# Timing_Control_V1p1.net
KiCad netlist of a schematic drawn in EAGLE
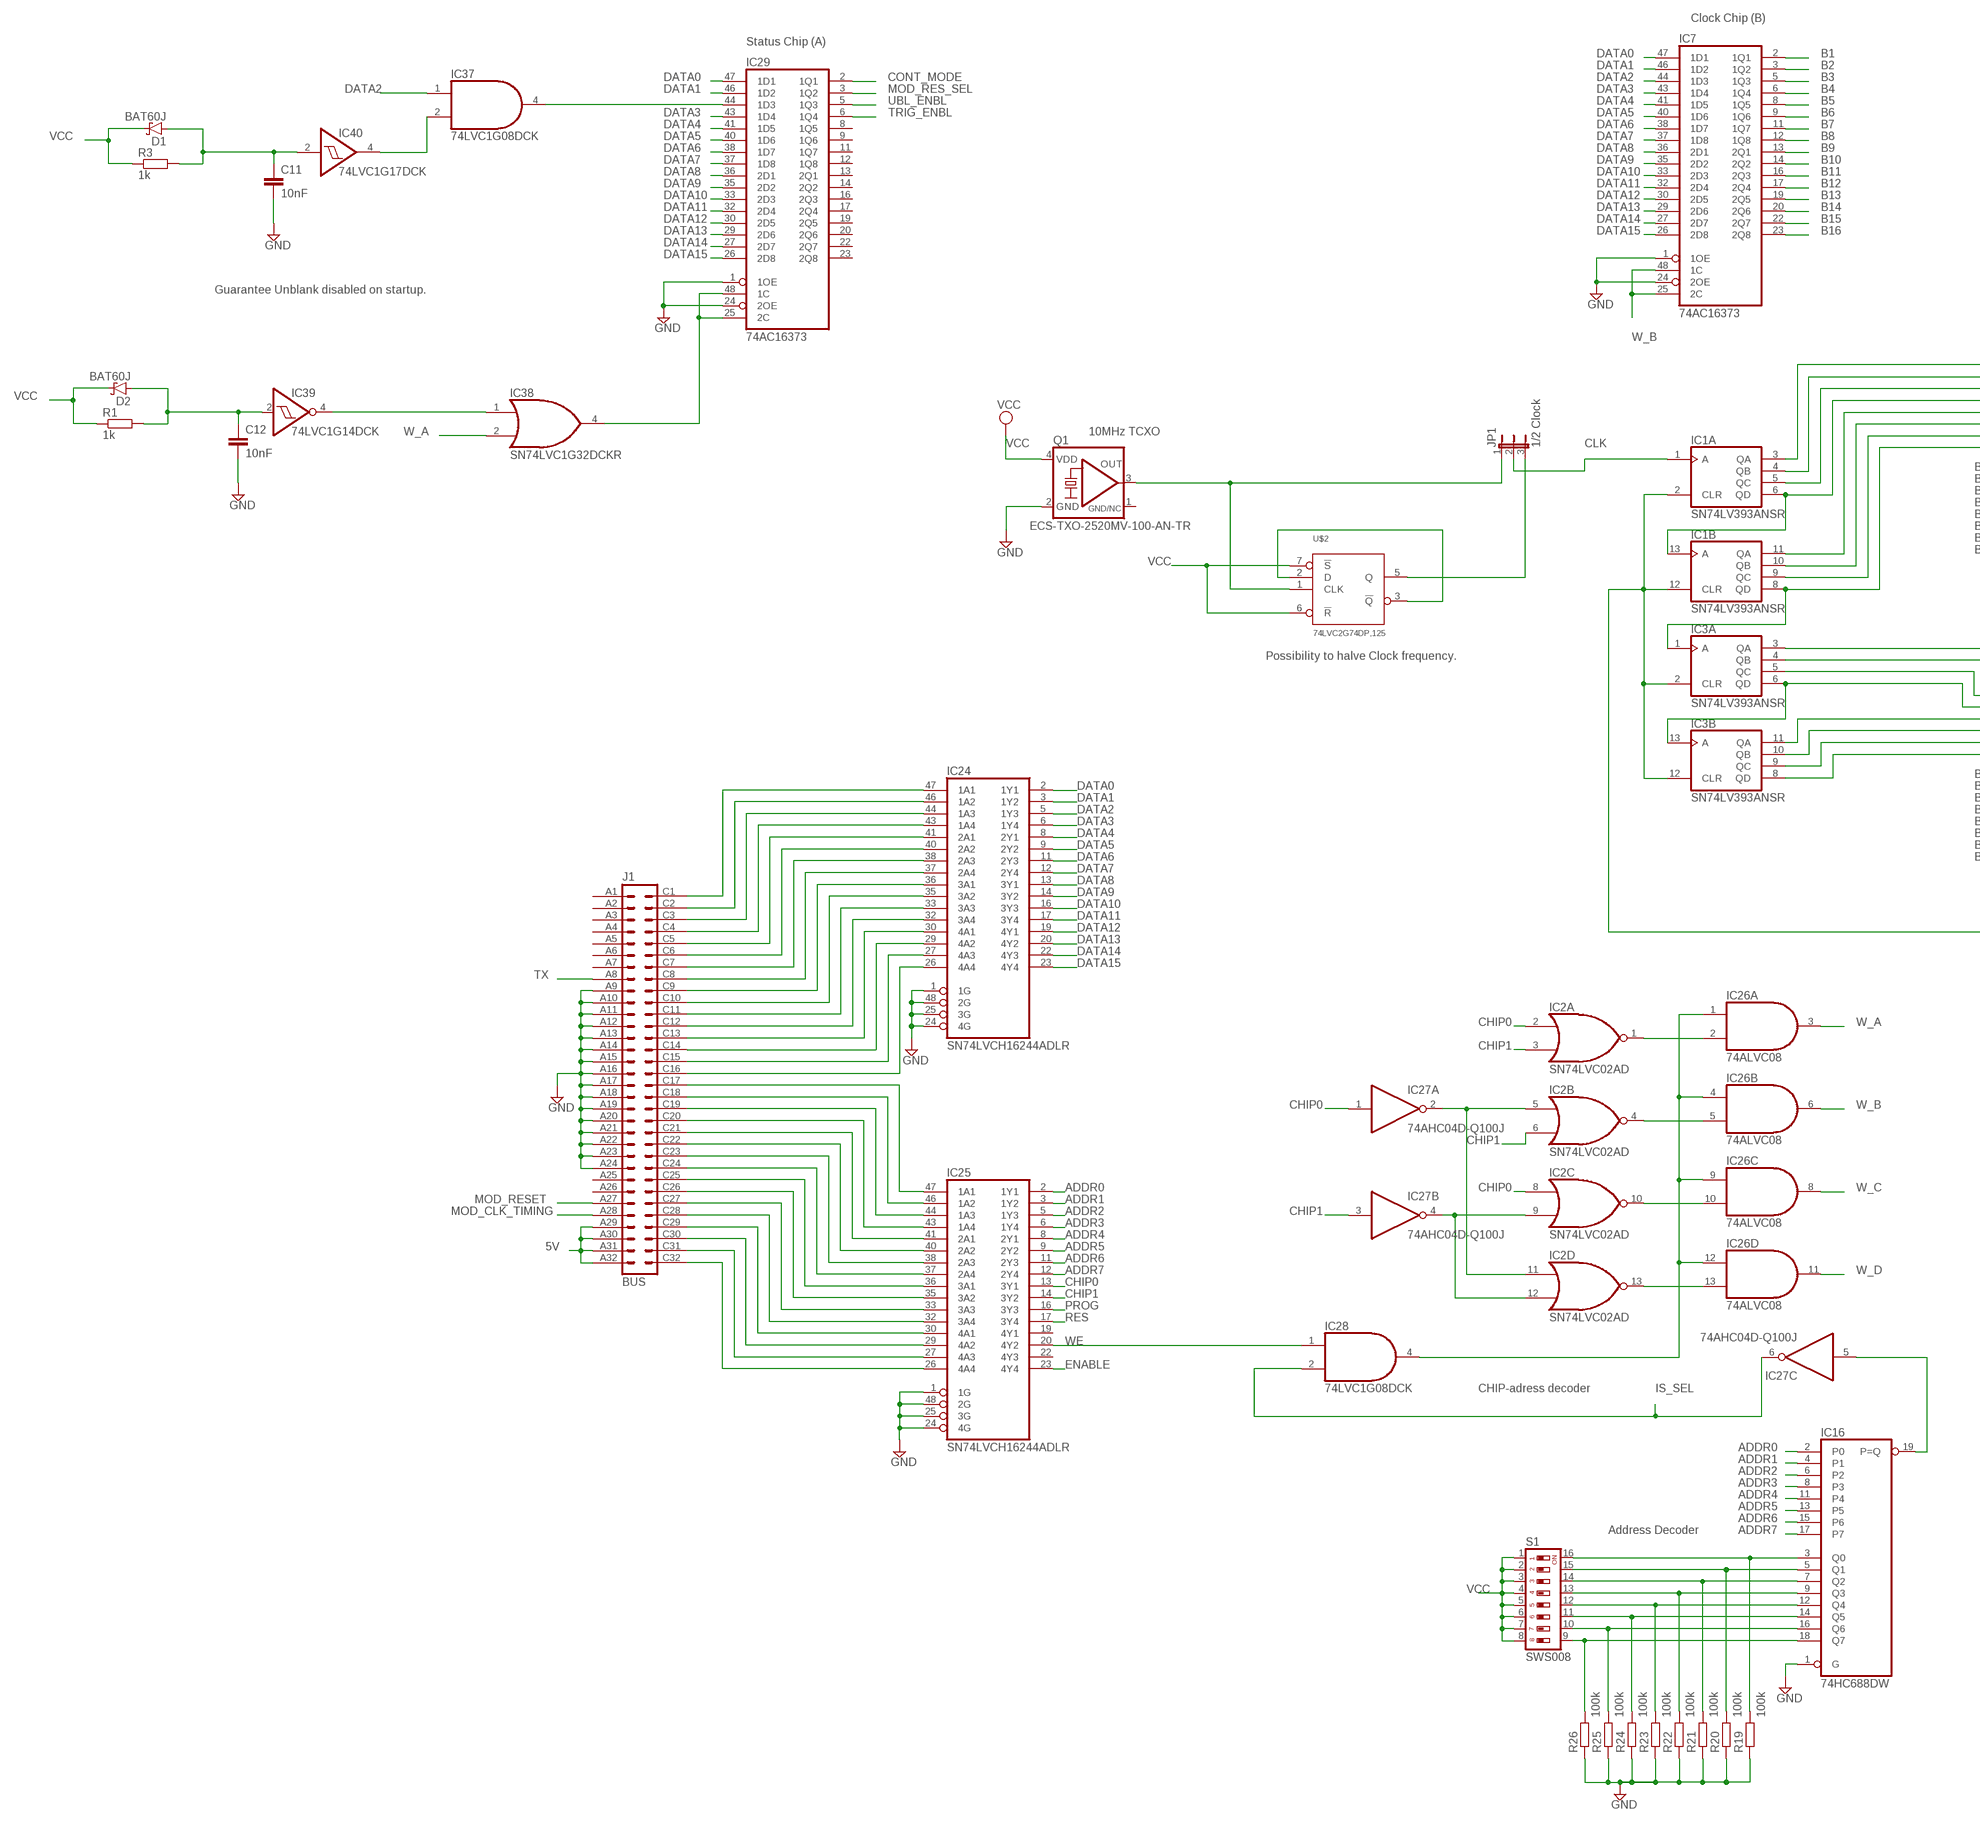
[diagram p0: schematic, sheet 1, part 1 of 3]
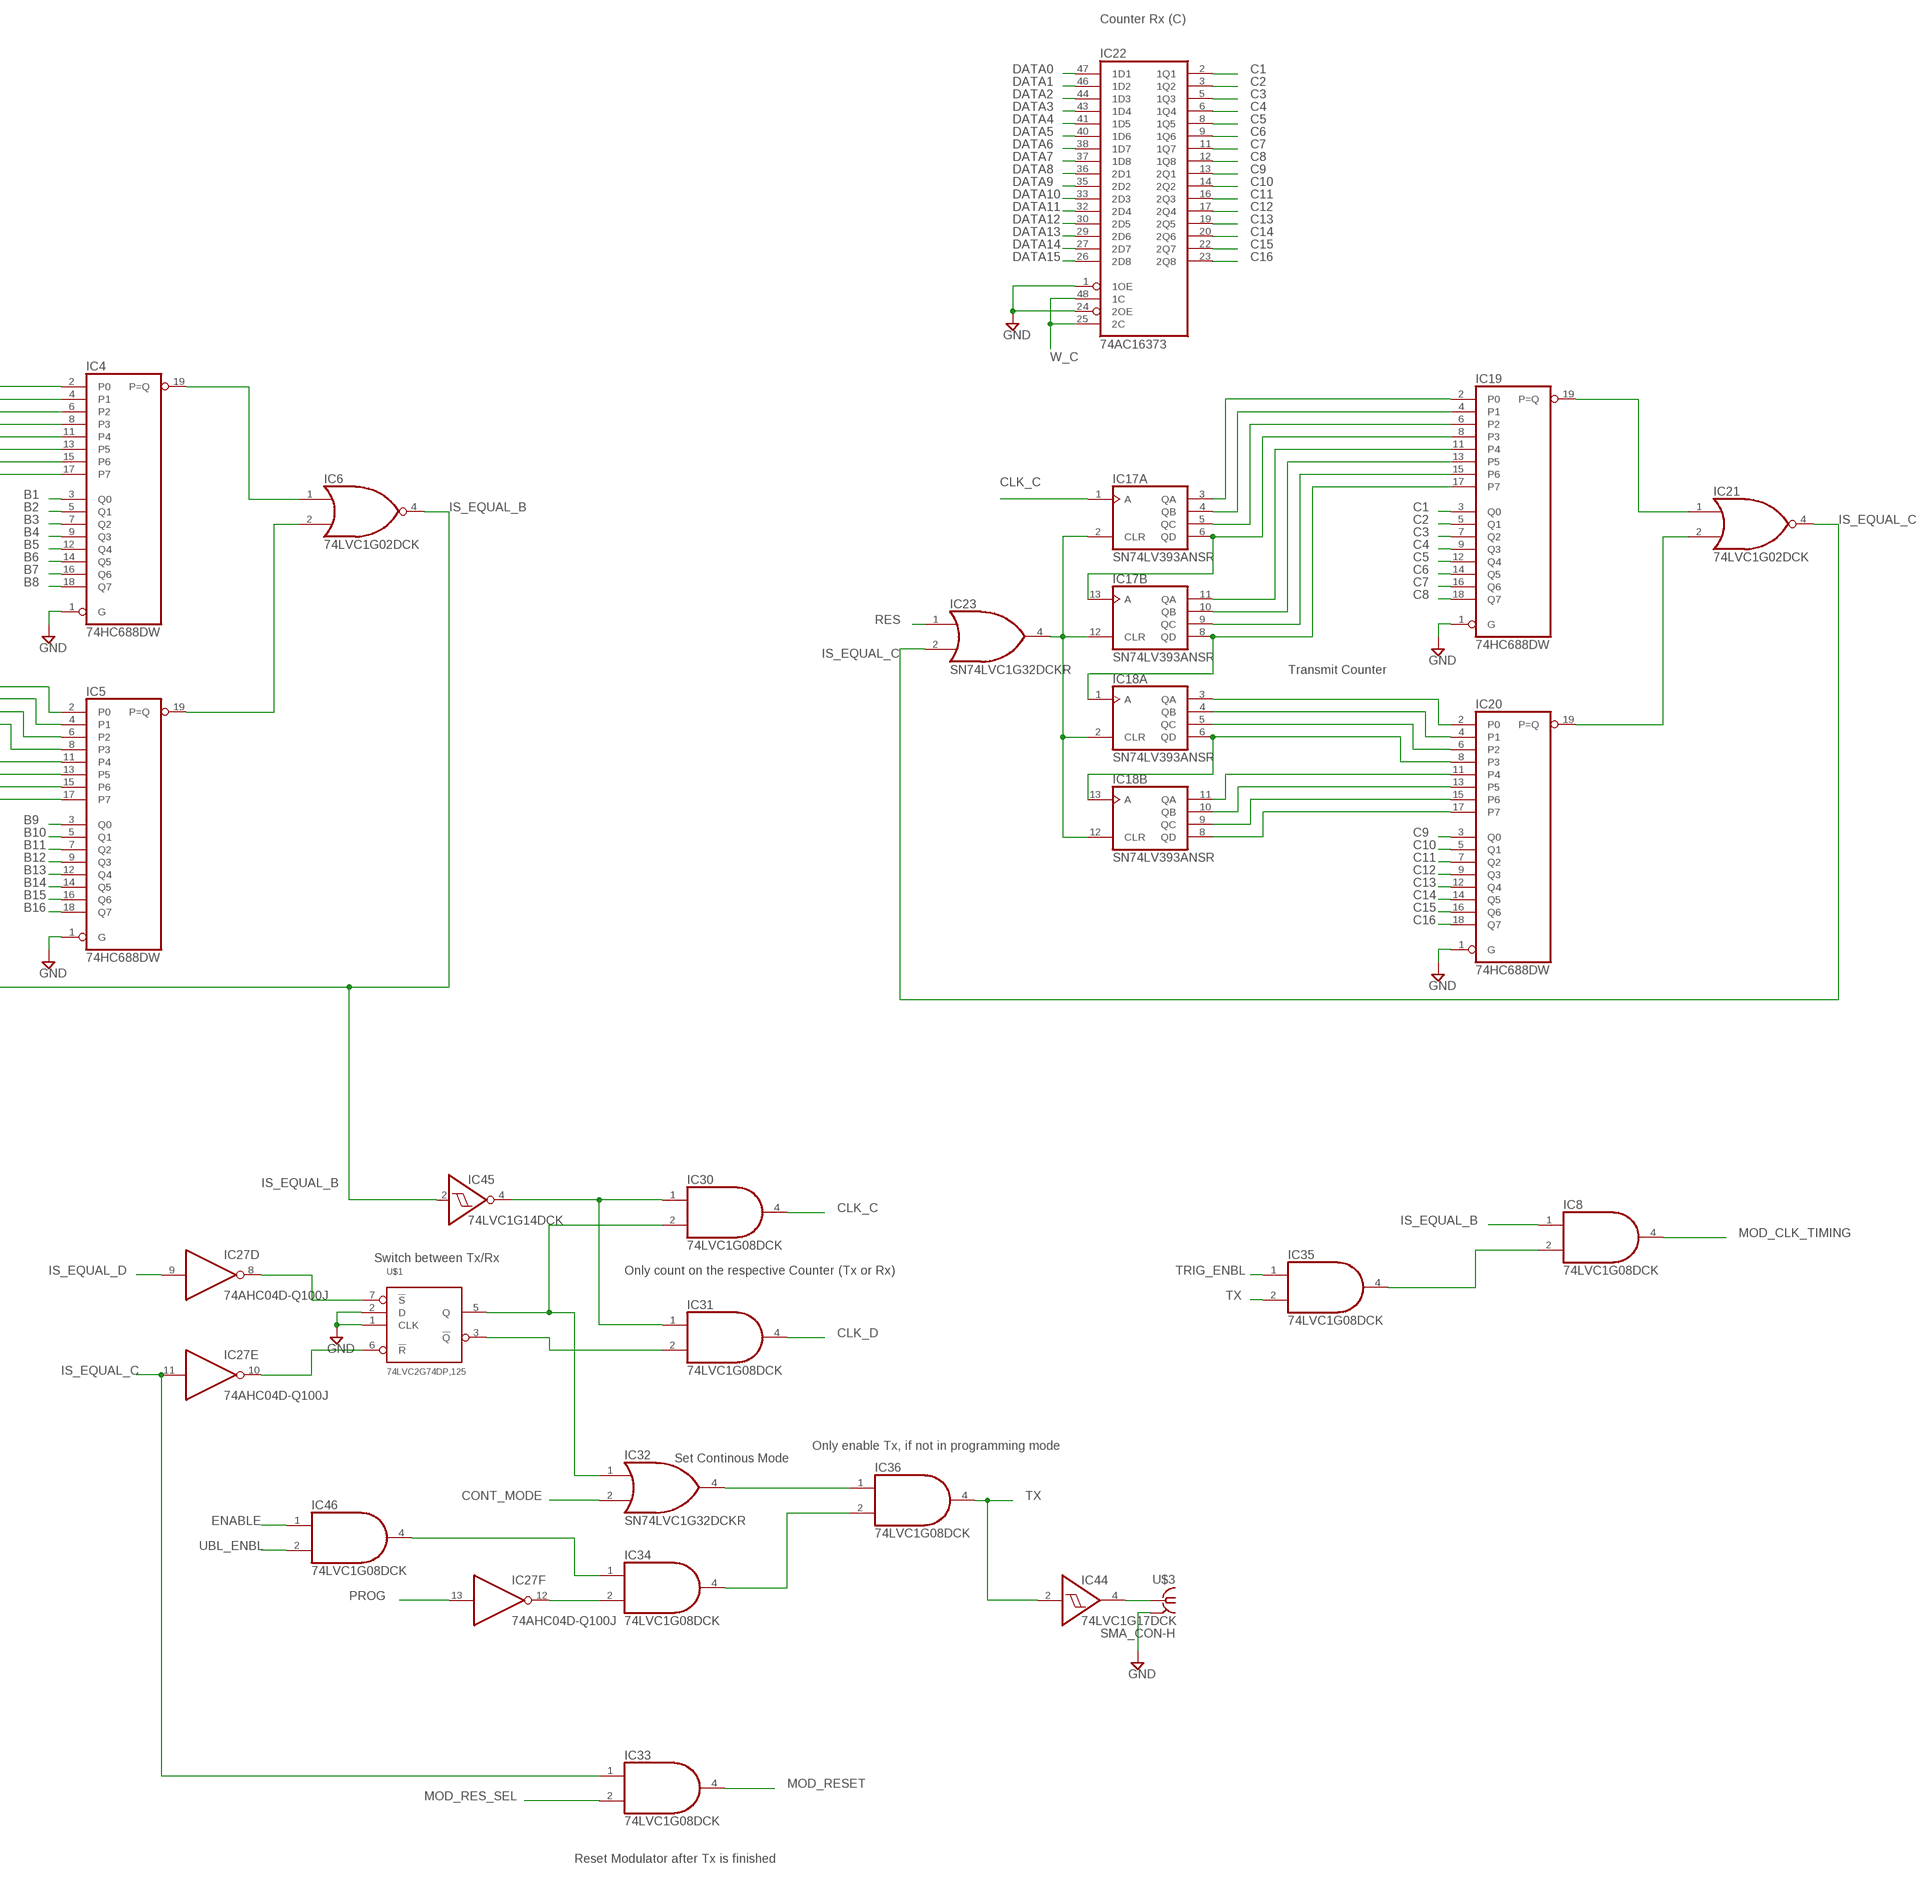
[diagram p1: schematic, sheet 1, part 2 of 3]
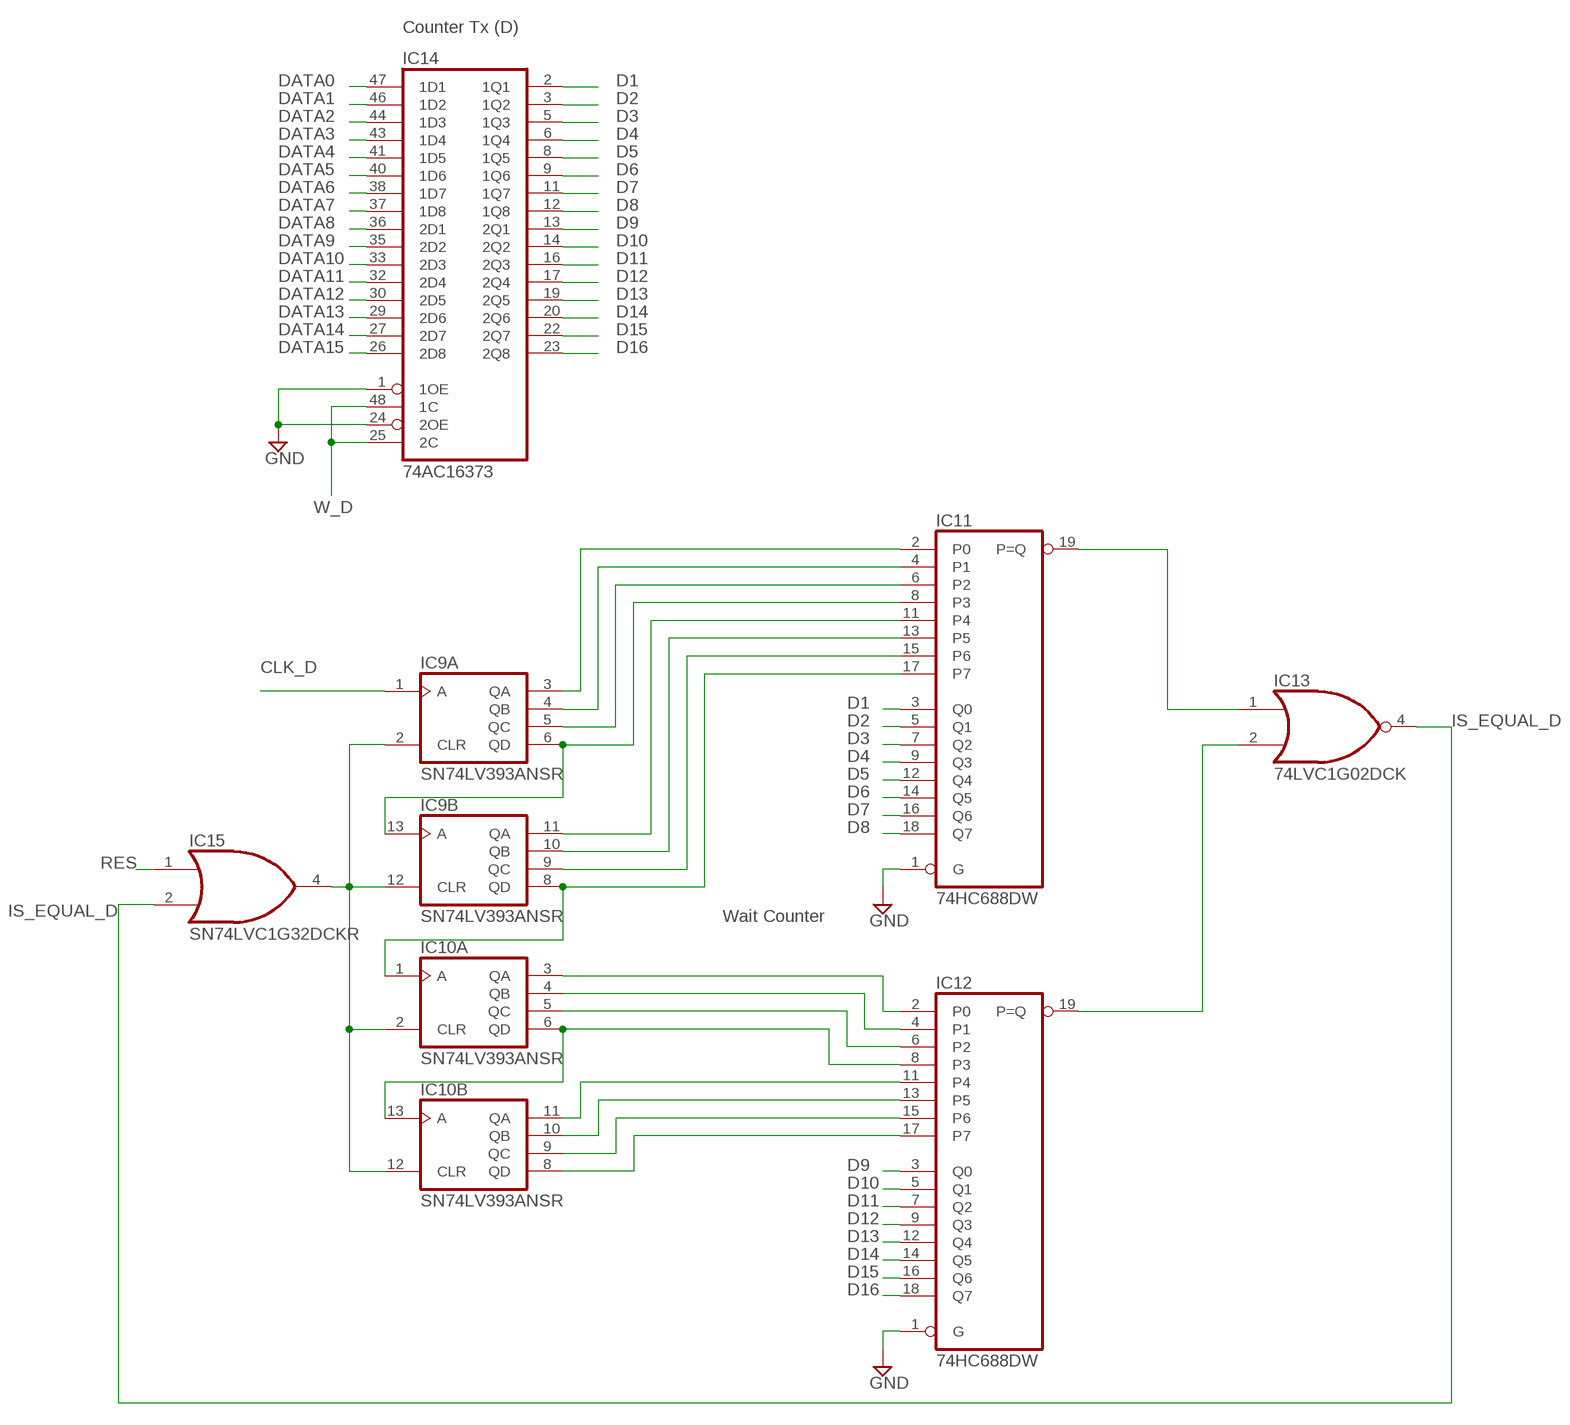
[diagram p2: schematic, sheet 1, part 3 of 3]
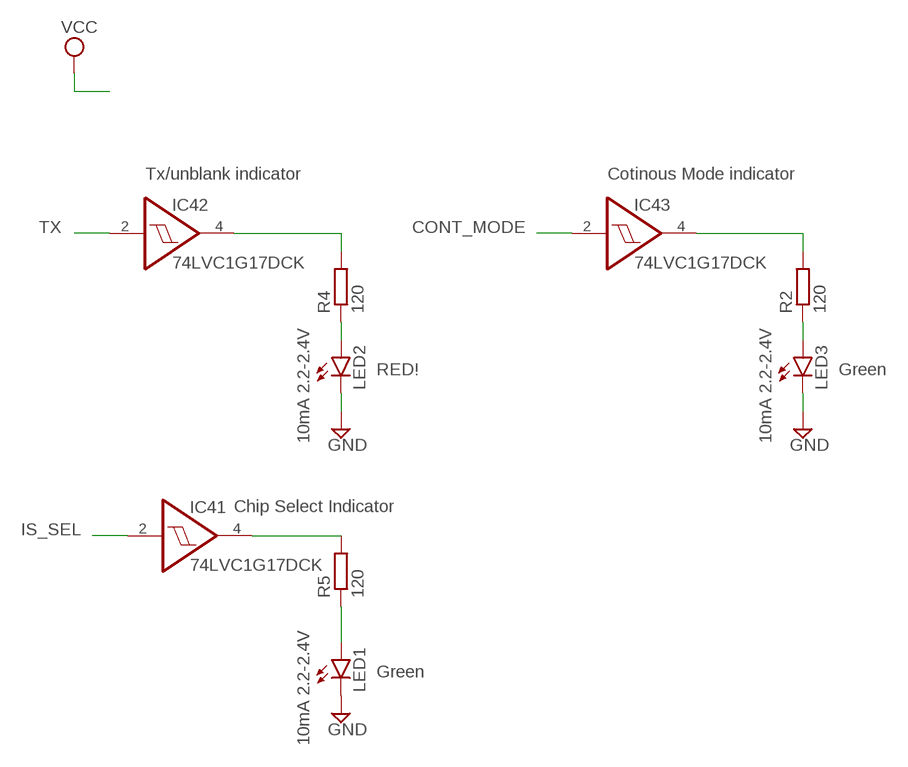
[diagram p3: schematic, sheet 2]
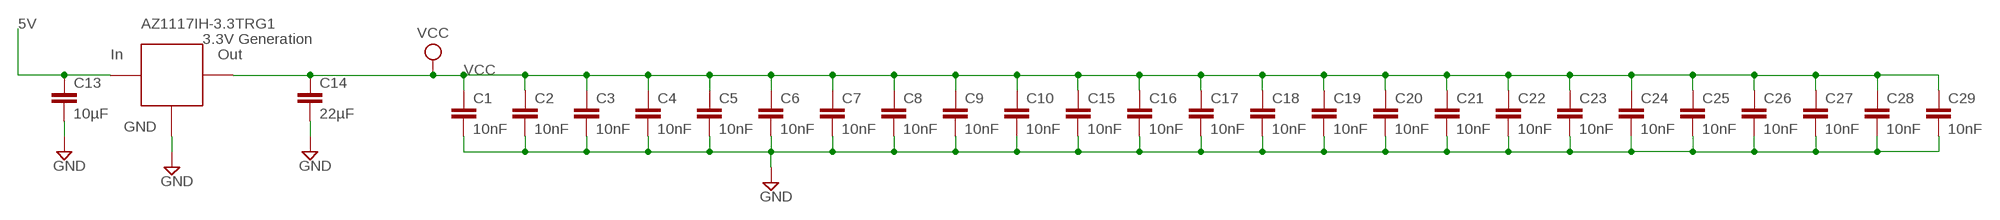
[diagram p4: schematic, sheet 3]

(export (version "E")
  (design (tool "Eeschema 10.0.6"))
  (components
    (comp (ref "C11")
      (value "10nF")
      (footprint "eagle-import:C0603")
      (libsource (lib "eagle-import") (part "C-EUC0603"))
    )
    (comp (ref "C12")
      (value "10nF")
      (footprint "eagle-import:C0603")
      (libsource (lib "eagle-import") (part "C-EUC0603"))
    )
    (comp (ref "D1")
      (value "BAT60J")
      (footprint "eagle-import:SOD323_ST")
      (libsource (lib "eagle-import") (part "BAT60J"))
    )
    (comp (ref "D2")
      (value "BAT60J")
      (footprint "eagle-import:SOD323_ST")
      (libsource (lib "eagle-import") (part "BAT60J"))
    )
    (comp (ref "IC1")
      (value "SN74LV393ANSR")
      (footprint "eagle-import:SO14")
      (libsource (lib "eagle-import") (part "74393DAC"))
    )
    (comp (ref "IC2")
      (value "SN74LVC02AD")
      (footprint "eagle-import:SO14")
      (libsource (lib "eagle-import") (part "7402DAS"))
    )
    (comp (ref "IC3")
      (value "SN74LV393ANSR")
      (footprint "eagle-import:SO14")
      (libsource (lib "eagle-import") (part "74393DAC"))
    )
    (comp (ref "IC4")
      (value "74HC688DW")
      (footprint "eagle-import:SO20W")
      (libsource (lib "eagle-import") (part "74688DWHC"))
    )
    (comp (ref "IC5")
      (value "74HC688DW")
      (footprint "eagle-import:SO20W")
      (libsource (lib "eagle-import") (part "74688DWHC"))
    )
    (comp (ref "IC6")
      (value "74LVC1G02DCK")
      (footprint "eagle-import:SC70-5")
      (libsource (lib "eagle-import") (part "741G02DCKLVC"))
    )
    (comp (ref "IC7")
      (value "74AC16373")
      (footprint "eagle-import:SSOP48DL")
      (libsource (lib "eagle-import") (part "74AC16373"))
    )
    (comp (ref "IC8")
      (value "74LVC1G08DCK")
      (footprint "eagle-import:SC70-5")
      (libsource (lib "eagle-import") (part "741G08DCKLVC"))
    )
    (comp (ref "IC9")
      (value "SN74LV393ANSR")
      (footprint "eagle-import:SO14")
      (libsource (lib "eagle-import") (part "74393DAC"))
    )
    (comp (ref "IC10")
      (value "SN74LV393ANSR")
      (footprint "eagle-import:SO14")
      (libsource (lib "eagle-import") (part "74393DAC"))
    )
    (comp (ref "IC11")
      (value "74HC688DW")
      (footprint "eagle-import:SO20W")
      (libsource (lib "eagle-import") (part "74688DWHC"))
    )
    (comp (ref "IC12")
      (value "74HC688DW")
      (footprint "eagle-import:SO20W")
      (libsource (lib "eagle-import") (part "74688DWHC"))
    )
    (comp (ref "IC13")
      (value "74LVC1G02DCK")
      (footprint "eagle-import:SC70-5")
      (libsource (lib "eagle-import") (part "741G02DCKLVC"))
    )
    (comp (ref "IC14")
      (value "74AC16373")
      (footprint "eagle-import:SSOP48DL")
      (libsource (lib "eagle-import") (part "74AC16373"))
    )
    (comp (ref "IC15")
      (value "SN74LVC1G32DCKR")
      (footprint "eagle-import:SC70-5")
      (libsource (lib "eagle-import") (part "741G32DCKAUC"))
    )
    (comp (ref "IC16")
      (value "74HC688DW")
      (footprint "eagle-import:SO20W")
      (libsource (lib "eagle-import") (part "74688DWHC"))
    )
    (comp (ref "IC17")
      (value "SN74LV393ANSR")
      (footprint "eagle-import:SO14")
      (libsource (lib "eagle-import") (part "74393DAC"))
    )
    (comp (ref "IC18")
      (value "SN74LV393ANSR")
      (footprint "eagle-import:SO14")
      (libsource (lib "eagle-import") (part "74393DAC"))
    )
    (comp (ref "IC19")
      (value "74HC688DW")
      (footprint "eagle-import:SO20W")
      (libsource (lib "eagle-import") (part "74688DWHC"))
    )
    (comp (ref "IC20")
      (value "74HC688DW")
      (footprint "eagle-import:SO20W")
      (libsource (lib "eagle-import") (part "74688DWHC"))
    )
    (comp (ref "IC21")
      (value "74LVC1G02DCK")
      (footprint "eagle-import:SC70-5")
      (libsource (lib "eagle-import") (part "741G02DCKLVC"))
    )
    (comp (ref "IC22")
      (value "74AC16373")
      (footprint "eagle-import:SSOP48DL")
      (libsource (lib "eagle-import") (part "74AC16373"))
    )
    (comp (ref "IC23")
      (value "SN74LVC1G32DCKR")
      (footprint "eagle-import:SC70-5")
      (libsource (lib "eagle-import") (part "741G32DCKAUC"))
    )
    (comp (ref "IC24")
      (value "SN74LVCH16244ADLR")
      (footprint "eagle-import:SSOP48DL")
      (libsource (lib "eagle-import") (part "74AC16244"))
    )
    (comp (ref "IC25")
      (value "SN74LVCH16244ADLR")
      (footprint "eagle-import:SSOP48DL")
      (libsource (lib "eagle-import") (part "74AC16244"))
    )
    (comp (ref "IC26")
      (value "74ALVC08")
      (footprint "eagle-import:SO14")
      (libsource (lib "eagle-import") (part "7408DALS"))
    )
    (comp (ref "IC27")
      (value "74AHC04D-Q100J")
      (footprint "eagle-import:SO14")
      (libsource (lib "eagle-import") (part "7404DALS"))
    )
    (comp (ref "IC28")
      (value "74LVC1G08DCK")
      (footprint "eagle-import:SC70-5")
      (libsource (lib "eagle-import") (part "741G08DCKLVC"))
    )
    (comp (ref "IC29")
      (value "74AC16373")
      (footprint "eagle-import:SSOP48DL")
      (libsource (lib "eagle-import") (part "74AC16373"))
    )
    (comp (ref "IC30")
      (value "74LVC1G08DCK")
      (footprint "eagle-import:SC70-5")
      (libsource (lib "eagle-import") (part "741G08DCKLVC"))
    )
    (comp (ref "IC31")
      (value "74LVC1G08DCK")
      (footprint "eagle-import:SC70-5")
      (libsource (lib "eagle-import") (part "741G08DCKLVC"))
    )
    (comp (ref "IC32")
      (value "SN74LVC1G32DCKR")
      (footprint "eagle-import:SC70-5")
      (libsource (lib "eagle-import") (part "741G32DCKAUC"))
    )
    (comp (ref "IC33")
      (value "74LVC1G08DCK")
      (footprint "eagle-import:SC70-5")
      (libsource (lib "eagle-import") (part "741G08DCKLVC"))
    )
    (comp (ref "IC34")
      (value "74LVC1G08DCK")
      (footprint "eagle-import:SC70-5")
      (libsource (lib "eagle-import") (part "741G08DCKLVC"))
    )
    (comp (ref "IC35")
      (value "74LVC1G08DCK")
      (footprint "eagle-import:SC70-5")
      (libsource (lib "eagle-import") (part "741G08DCKLVC"))
    )
    (comp (ref "IC36")
      (value "74LVC1G08DCK")
      (footprint "eagle-import:SC70-5")
      (libsource (lib "eagle-import") (part "741G08DCKLVC"))
    )
    (comp (ref "IC37")
      (value "74LVC1G08DCK")
      (footprint "eagle-import:SC70-5")
      (libsource (lib "eagle-import") (part "741G08DCKLVC"))
    )
    (comp (ref "IC38")
      (value "SN74LVC1G32DCKR")
      (footprint "eagle-import:SC70-5")
      (libsource (lib "eagle-import") (part "741G32DCKAUC"))
    )
    (comp (ref "IC39")
      (value "74LVC1G14DCK")
      (footprint "eagle-import:SC70-5")
      (libsource (lib "eagle-import") (part "741G14DCKLVC"))
    )
    (comp (ref "IC40")
      (value "74LVC1G17DCK")
      (footprint "eagle-import:SC70-5")
      (libsource (lib "eagle-import") (part "741G17DCKLVC"))
    )
    (comp (ref "IC44")
      (value "74LVC1G17DCK")
      (footprint "eagle-import:SC70-5")
      (libsource (lib "eagle-import") (part "741G17DCKLVC"))
    )
    (comp (ref "IC45")
      (value "74LVC1G14DCK")
      (footprint "eagle-import:SC70-5")
      (libsource (lib "eagle-import") (part "741G14DCKLVC"))
    )
    (comp (ref "IC46")
      (value "74LVC1G08DCK")
      (footprint "eagle-import:SC70-5")
      (libsource (lib "eagle-import") (part "741G08DCKLVC"))
    )
    (comp (ref "J1")
      (value "BUS")
      (footprint "eagle-import:VG64P")
      (libsource (lib "eagle-import") (part "VG64P"))
    )
    (comp (ref "JP1")
      (value "1/2 Clock")
      (footprint "eagle-import:JP2")
      (libsource (lib "eagle-import") (part "JP2E"))
    )
    (comp (ref "Q1")
      (value "ECS-TXO-2520MV-100-AN-TR")
      (footprint "eagle-import:2.5X2.0_KXO-86-TCXO")
      (libsource (lib "eagle-import") (part "KXO-TCXO-CMOS-86"))
    )
    (comp (ref "R1")
      (value "1k")
      (footprint "eagle-import:R0603")
      (libsource (lib "eagle-import") (part "R-EU_R0603"))
    )
    (comp (ref "R3")
      (value "1k")
      (footprint "eagle-import:R0603")
      (libsource (lib "eagle-import") (part "R-EU_R0603"))
    )
    (comp (ref "R19")
      (value "100k")
      (footprint "eagle-import:R0603")
      (libsource (lib "eagle-import") (part "R-EU_R0603"))
    )
    (comp (ref "R20")
      (value "100k")
      (footprint "eagle-import:R0603")
      (libsource (lib "eagle-import") (part "R-EU_R0603"))
    )
    (comp (ref "R21")
      (value "100k")
      (footprint "eagle-import:R0603")
      (libsource (lib "eagle-import") (part "R-EU_R0603"))
    )
    (comp (ref "R22")
      (value "100k")
      (footprint "eagle-import:R0603")
      (libsource (lib "eagle-import") (part "R-EU_R0603"))
    )
    (comp (ref "R23")
      (value "100k")
      (footprint "eagle-import:R0603")
      (libsource (lib "eagle-import") (part "R-EU_R0603"))
    )
    (comp (ref "R24")
      (value "100k")
      (footprint "eagle-import:R0603")
      (libsource (lib "eagle-import") (part "R-EU_R0603"))
    )
    (comp (ref "R25")
      (value "100k")
      (footprint "eagle-import:R0603")
      (libsource (lib "eagle-import") (part "R-EU_R0603"))
    )
    (comp (ref "R26")
      (value "100k")
      (footprint "eagle-import:R0603")
      (libsource (lib "eagle-import") (part "R-EU_R0603"))
    )
    (comp (ref "S1")
      (value "SWS008")
      (footprint "eagle-import:SMS-008")
      (libsource (lib "eagle-import") (part "SWS008"))
    )
    (comp (ref "U$1")
      (value "74LVC2G74DP,125")
      (footprint "eagle-import:SSOP08")
      (libsource (lib "eagle-import") (part "74LVC2G74"))
    )
    (comp (ref "U$2")
      (value "74LVC2G74DP,125")
      (footprint "eagle-import:SSOP08")
      (libsource (lib "eagle-import") (part "74LVC2G74"))
    )
    (comp (ref "U$3")
      (value "SMA_CON-H")
      (footprint "eagle-import:BU-SMA-H")
      (libsource (lib "eagle-import") (part "SMA_CON-H"))
    )
    (comp (ref "C1")
      (value "10nF")
      (footprint "eagle-import:C0603")
      (libsource (lib "eagle-import") (part "C-EUC0603"))
    )
    (comp (ref "C2")
      (value "10nF")
      (footprint "eagle-import:C0603")
      (libsource (lib "eagle-import") (part "C-EUC0603"))
    )
    (comp (ref "C3")
      (value "10nF")
      (footprint "eagle-import:C0603")
      (libsource (lib "eagle-import") (part "C-EUC0603"))
    )
    (comp (ref "C4")
      (value "10nF")
      (footprint "eagle-import:C0603")
      (libsource (lib "eagle-import") (part "C-EUC0603"))
    )
    (comp (ref "C5")
      (value "10nF")
      (footprint "eagle-import:C0603")
      (libsource (lib "eagle-import") (part "C-EUC0603"))
    )
    (comp (ref "C6")
      (value "10nF")
      (footprint "eagle-import:C0603")
      (libsource (lib "eagle-import") (part "C-EUC0603"))
    )
    (comp (ref "C7")
      (value "10nF")
      (footprint "eagle-import:C0603")
      (libsource (lib "eagle-import") (part "C-EUC0603"))
    )
    (comp (ref "C8")
      (value "10nF")
      (footprint "eagle-import:C0603")
      (libsource (lib "eagle-import") (part "C-EUC0603"))
    )
    (comp (ref "C9")
      (value "10nF")
      (footprint "eagle-import:C0603")
      (libsource (lib "eagle-import") (part "C-EUC0603"))
    )
    (comp (ref "C10")
      (value "10nF")
      (footprint "eagle-import:C0603")
      (libsource (lib "eagle-import") (part "C-EUC0603"))
    )
    (comp (ref "C13")
      (value "10µF")
      (footprint "eagle-import:C1206")
      (libsource (lib "eagle-import") (part "C-EUC1206"))
    )
    (comp (ref "C14")
      (value "22µF")
      (footprint "eagle-import:C1206")
      (libsource (lib "eagle-import") (part "C-EUC1206"))
    )
    (comp (ref "C15")
      (value "10nF")
      (footprint "eagle-import:C0603")
      (libsource (lib "eagle-import") (part "C-EUC0603"))
    )
    (comp (ref "C16")
      (value "10nF")
      (footprint "eagle-import:C0603")
      (libsource (lib "eagle-import") (part "C-EUC0603"))
    )
    (comp (ref "C17")
      (value "10nF")
      (footprint "eagle-import:C0603")
      (libsource (lib "eagle-import") (part "C-EUC0603"))
    )
    (comp (ref "C18")
      (value "10nF")
      (footprint "eagle-import:C0603")
      (libsource (lib "eagle-import") (part "C-EUC0603"))
    )
    (comp (ref "C19")
      (value "10nF")
      (footprint "eagle-import:C0603")
      (libsource (lib "eagle-import") (part "C-EUC0603"))
    )
    (comp (ref "C20")
      (value "10nF")
      (footprint "eagle-import:C0603")
      (libsource (lib "eagle-import") (part "C-EUC0603"))
    )
    (comp (ref "C21")
      (value "10nF")
      (footprint "eagle-import:C0603")
      (libsource (lib "eagle-import") (part "C-EUC0603"))
    )
    (comp (ref "C22")
      (value "10nF")
      (footprint "eagle-import:C0603")
      (libsource (lib "eagle-import") (part "C-EUC0603"))
    )
    (comp (ref "C23")
      (value "10nF")
      (footprint "eagle-import:C0603")
      (libsource (lib "eagle-import") (part "C-EUC0603"))
    )
    (comp (ref "C24")
      (value "10nF")
      (footprint "eagle-import:C0603")
      (libsource (lib "eagle-import") (part "C-EUC0603"))
    )
    (comp (ref "C25")
      (value "10nF")
      (footprint "eagle-import:C0603")
      (libsource (lib "eagle-import") (part "C-EUC0603"))
    )
    (comp (ref "C26")
      (value "10nF")
      (footprint "eagle-import:C0603")
      (libsource (lib "eagle-import") (part "C-EUC0603"))
    )
    (comp (ref "C27")
      (value "10nF")
      (footprint "eagle-import:C0603")
      (libsource (lib "eagle-import") (part "C-EUC0603"))
    )
    (comp (ref "C28")
      (value "10nF")
      (footprint "eagle-import:C0603")
      (libsource (lib "eagle-import") (part "C-EUC0603"))
    )
    (comp (ref "C29")
      (value "10nF")
      (footprint "eagle-import:C0603")
      (libsource (lib "eagle-import") (part "C-EUC0603"))
    )
    (comp (ref "U$9")
      (value "AZ1117IH-3.3TRG1")
      (footprint "eagle-import:SOT223")
      (libsource (lib "eagle-import") (part "LT1117"))
    )
    (comp (ref "IC41")
      (value "74LVC1G17DCK")
      (footprint "eagle-import:SC70-5")
      (libsource (lib "eagle-import") (part "741G17DCKLVC"))
    )
    (comp (ref "IC42")
      (value "74LVC1G17DCK")
      (footprint "eagle-import:SC70-5")
      (libsource (lib "eagle-import") (part "741G17DCKLVC"))
    )
    (comp (ref "IC43")
      (value "74LVC1G17DCK")
      (footprint "eagle-import:SC70-5")
      (libsource (lib "eagle-import") (part "741G17DCKLVC"))
    )
    (comp (ref "LED1")
      (value "10mA 2.2-2.4V")
      (footprint "eagle-import:LED3MM")
      (libsource (lib "eagle-import") (part "LED3MM"))
    )
    (comp (ref "LED2")
      (value "10mA 2.2-2.4V")
      (footprint "eagle-import:LED3MM")
      (libsource (lib "eagle-import") (part "LED3MM"))
    )
    (comp (ref "LED3")
      (value "10mA 2.2-2.4V")
      (footprint "eagle-import:LED3MM")
      (libsource (lib "eagle-import") (part "LED3MM"))
    )
    (comp (ref "R2")
      (value "120")
      (footprint "eagle-import:R0603")
      (libsource (lib "eagle-import") (part "R-EU_R0603"))
    )
    (comp (ref "R4")
      (value "120")
      (footprint "eagle-import:R0603")
      (libsource (lib "eagle-import") (part "R-EU_R0603"))
    )
    (comp (ref "R5")
      (value "120")
      (footprint "eagle-import:R0603")
      (libsource (lib "eagle-import") (part "R-EU_R0603"))
    )
  )
  (nets
    (net (code "1") (name "5V") (class "Default")
      (node (ref "C13") (pin "1") (pinfunction "1_1") (pintype "passive"))
      (node (ref "J1") (pin "A29") (pinfunction "A29_A29") (pintype "passive"))
      (node (ref "J1") (pin "A30") (pinfunction "A30_A30") (pintype "passive"))
      (node (ref "J1") (pin "A31") (pinfunction "A31_A31") (pintype "passive"))
      (node (ref "J1") (pin "A32") (pinfunction "A32_A32") (pintype "passive"))
      (node (ref "U$9") (pin "3") (pinfunction "IN_3") (pintype "bidirectional"))
    )
    (net (code "2") (name "ADDR0") (class "Default")
      (node (ref "IC16") (pin "2") (pinfunction "P0_2") (pintype "input"))
      (node (ref "IC25") (pin "2") (pinfunction "1Y1_2") (pintype "tri_state"))
    )
    (net (code "3") (name "ADDR1") (class "Default")
      (node (ref "IC16") (pin "4") (pinfunction "P1_4") (pintype "input"))
      (node (ref "IC25") (pin "3") (pinfunction "1Y2_3") (pintype "tri_state"))
    )
    (net (code "4") (name "ADDR2") (class "Default")
      (node (ref "IC16") (pin "6") (pinfunction "P2_6") (pintype "input"))
      (node (ref "IC25") (pin "5") (pinfunction "1Y3_5") (pintype "tri_state"))
    )
    (net (code "5") (name "ADDR3") (class "Default")
      (node (ref "IC16") (pin "8") (pinfunction "P3_8") (pintype "input"))
      (node (ref "IC25") (pin "6") (pinfunction "1Y4_6") (pintype "tri_state"))
    )
    (net (code "6") (name "ADDR4") (class "Default")
      (node (ref "IC16") (pin "11") (pinfunction "P4_11") (pintype "input"))
      (node (ref "IC25") (pin "8") (pinfunction "2Y1_8") (pintype "tri_state"))
    )
    (net (code "7") (name "ADDR5") (class "Default")
      (node (ref "IC16") (pin "13") (pinfunction "P5_13") (pintype "input"))
      (node (ref "IC25") (pin "9") (pinfunction "2Y2_9") (pintype "tri_state"))
    )
    (net (code "8") (name "ADDR6") (class "Default")
      (node (ref "IC16") (pin "15") (pinfunction "P6_15") (pintype "input"))
      (node (ref "IC25") (pin "11") (pinfunction "2Y3_11") (pintype "tri_state"))
    )
    (net (code "9") (name "ADDR7") (class "Default")
      (node (ref "IC16") (pin "17") (pinfunction "P7_17") (pintype "input"))
      (node (ref "IC25") (pin "12") (pinfunction "2Y4_12") (pintype "tri_state"))
    )
    (net (code "10") (name "B1") (class "Default")
      (node (ref "IC4") (pin "3") (pinfunction "Q0_3") (pintype "input"))
      (node (ref "IC7") (pin "2") (pinfunction "1Q1_2") (pintype "tri_state"))
    )
    (net (code "11") (name "B2") (class "Default")
      (node (ref "IC4") (pin "5") (pinfunction "Q1_5") (pintype "input"))
      (node (ref "IC7") (pin "3") (pinfunction "1Q2_3") (pintype "tri_state"))
    )
    (net (code "12") (name "B3") (class "Default")
      (node (ref "IC4") (pin "7") (pinfunction "Q2_7") (pintype "input"))
      (node (ref "IC7") (pin "5") (pinfunction "1Q3_5") (pintype "tri_state"))
    )
    (net (code "13") (name "B4") (class "Default")
      (node (ref "IC4") (pin "9") (pinfunction "Q3_9") (pintype "input"))
      (node (ref "IC7") (pin "6") (pinfunction "1Q4_6") (pintype "tri_state"))
    )
    (net (code "14") (name "B5") (class "Default")
      (node (ref "IC4") (pin "12") (pinfunction "Q4_12") (pintype "input"))
      (node (ref "IC7") (pin "8") (pinfunction "1Q5_8") (pintype "tri_state"))
    )
    (net (code "15") (name "B6") (class "Default")
      (node (ref "IC4") (pin "14") (pinfunction "Q5_14") (pintype "input"))
      (node (ref "IC7") (pin "9") (pinfunction "1Q6_9") (pintype "tri_state"))
    )
    (net (code "16") (name "B7") (class "Default")
      (node (ref "IC4") (pin "16") (pinfunction "Q6_16") (pintype "input"))
      (node (ref "IC7") (pin "11") (pinfunction "1Q7_11") (pintype "tri_state"))
    )
    (net (code "17") (name "B8") (class "Default")
      (node (ref "IC4") (pin "18") (pinfunction "Q7_18") (pintype "input"))
      (node (ref "IC7") (pin "12") (pinfunction "1Q8_12") (pintype "tri_state"))
    )
    (net (code "18") (name "B9") (class "Default")
      (node (ref "IC5") (pin "3") (pinfunction "Q0_3") (pintype "input"))
      (node (ref "IC7") (pin "13") (pinfunction "2Q1_13") (pintype "tri_state"))
    )
    (net (code "19") (name "B10") (class "Default")
      (node (ref "IC5") (pin "5") (pinfunction "Q1_5") (pintype "input"))
      (node (ref "IC7") (pin "14") (pinfunction "2Q2_14") (pintype "tri_state"))
    )
    (net (code "20") (name "B11") (class "Default")
      (node (ref "IC5") (pin "7") (pinfunction "Q2_7") (pintype "input"))
      (node (ref "IC7") (pin "16") (pinfunction "2Q3_16") (pintype "tri_state"))
    )
    (net (code "21") (name "B12") (class "Default")
      (node (ref "IC5") (pin "9") (pinfunction "Q3_9") (pintype "input"))
      (node (ref "IC7") (pin "17") (pinfunction "2Q4_17") (pintype "tri_state"))
    )
    (net (code "22") (name "B13") (class "Default")
      (node (ref "IC5") (pin "12") (pinfunction "Q4_12") (pintype "input"))
      (node (ref "IC7") (pin "19") (pinfunction "2Q5_19") (pintype "tri_state"))
    )
    (net (code "23") (name "B14") (class "Default")
      (node (ref "IC5") (pin "14") (pinfunction "Q5_14") (pintype "input"))
      (node (ref "IC7") (pin "20") (pinfunction "2Q6_20") (pintype "tri_state"))
    )
    (net (code "24") (name "B15") (class "Default")
      (node (ref "IC5") (pin "16") (pinfunction "Q6_16") (pintype "input"))
      (node (ref "IC7") (pin "22") (pinfunction "2Q7_22") (pintype "tri_state"))
    )
    (net (code "25") (name "B16") (class "Default")
      (node (ref "IC5") (pin "18") (pinfunction "Q7_18") (pintype "input"))
      (node (ref "IC7") (pin "23") (pinfunction "2Q8_23") (pintype "tri_state"))
    )
    (net (code "26") (name "C1") (class "Default")
      (node (ref "IC19") (pin "3") (pinfunction "Q0_3") (pintype "input"))
      (node (ref "IC22") (pin "2") (pinfunction "1Q1_2") (pintype "tri_state"))
    )
    (net (code "27") (name "C2") (class "Default")
      (node (ref "IC19") (pin "5") (pinfunction "Q1_5") (pintype "input"))
      (node (ref "IC22") (pin "3") (pinfunction "1Q2_3") (pintype "tri_state"))
    )
    (net (code "28") (name "C3") (class "Default")
      (node (ref "IC19") (pin "7") (pinfunction "Q2_7") (pintype "input"))
      (node (ref "IC22") (pin "5") (pinfunction "1Q3_5") (pintype "tri_state"))
    )
    (net (code "29") (name "C4") (class "Default")
      (node (ref "IC19") (pin "9") (pinfunction "Q3_9") (pintype "input"))
      (node (ref "IC22") (pin "6") (pinfunction "1Q4_6") (pintype "tri_state"))
    )
    (net (code "30") (name "C5") (class "Default")
      (node (ref "IC19") (pin "12") (pinfunction "Q4_12") (pintype "input"))
      (node (ref "IC22") (pin "8") (pinfunction "1Q5_8") (pintype "tri_state"))
    )
    (net (code "31") (name "C6") (class "Default")
      (node (ref "IC19") (pin "14") (pinfunction "Q5_14") (pintype "input"))
      (node (ref "IC22") (pin "9") (pinfunction "1Q6_9") (pintype "tri_state"))
    )
    (net (code "32") (name "C7") (class "Default")
      (node (ref "IC19") (pin "16") (pinfunction "Q6_16") (pintype "input"))
      (node (ref "IC22") (pin "11") (pinfunction "1Q7_11") (pintype "tri_state"))
    )
    (net (code "33") (name "C8") (class "Default")
      (node (ref "IC19") (pin "18") (pinfunction "Q7_18") (pintype "input"))
      (node (ref "IC22") (pin "12") (pinfunction "1Q8_12") (pintype "tri_state"))
    )
    (net (code "34") (name "C9") (class "Default")
      (node (ref "IC20") (pin "3") (pinfunction "Q0_3") (pintype "input"))
      (node (ref "IC22") (pin "13") (pinfunction "2Q1_13") (pintype "tri_state"))
    )
    (net (code "35") (name "C10") (class "Default")
      (node (ref "IC20") (pin "5") (pinfunction "Q1_5") (pintype "input"))
      (node (ref "IC22") (pin "14") (pinfunction "2Q2_14") (pintype "tri_state"))
    )
    (net (code "36") (name "C11") (class "Default")
      (node (ref "IC20") (pin "7") (pinfunction "Q2_7") (pintype "input"))
      (node (ref "IC22") (pin "16") (pinfunction "2Q3_16") (pintype "tri_state"))
    )
    (net (code "37") (name "C12") (class "Default")
      (node (ref "IC20") (pin "9") (pinfunction "Q3_9") (pintype "input"))
      (node (ref "IC22") (pin "17") (pinfunction "2Q4_17") (pintype "tri_state"))
    )
    (net (code "38") (name "C13") (class "Default")
      (node (ref "IC20") (pin "12") (pinfunction "Q4_12") (pintype "input"))
      (node (ref "IC22") (pin "19") (pinfunction "2Q5_19") (pintype "tri_state"))
    )
    (net (code "39") (name "C14") (class "Default")
      (node (ref "IC20") (pin "14") (pinfunction "Q5_14") (pintype "input"))
      (node (ref "IC22") (pin "20") (pinfunction "2Q6_20") (pintype "tri_state"))
    )
    (net (code "40") (name "C15") (class "Default")
      (node (ref "IC20") (pin "16") (pinfunction "Q6_16") (pintype "input"))
      (node (ref "IC22") (pin "22") (pinfunction "2Q7_22") (pintype "tri_state"))
    )
    (net (code "41") (name "C16") (class "Default")
      (node (ref "IC20") (pin "18") (pinfunction "Q7_18") (pintype "input"))
      (node (ref "IC22") (pin "23") (pinfunction "2Q8_23") (pintype "tri_state"))
    )
    (net (code "42") (name "CHIP0") (class "Default")
      (node (ref "IC2") (pin "2") (pinfunction "I0_2") (pintype "input"))
      (node (ref "IC2") (pin "8") (pinfunction "I0_8") (pintype "input"))
      (node (ref "IC25") (pin "13") (pinfunction "3Y1_13") (pintype "tri_state"))
      (node (ref "IC27") (pin "1") (pinfunction "I_1") (pintype "input"))
    )
    (net (code "43") (name "CHIP1") (class "Default")
      (node (ref "IC2") (pin "3") (pinfunction "I1_3") (pintype "input"))
      (node (ref "IC2") (pin "6") (pinfunction "I1_6") (pintype "input"))
      (node (ref "IC25") (pin "14") (pinfunction "3Y2_14") (pintype "tri_state"))
      (node (ref "IC27") (pin "3") (pinfunction "I_3") (pintype "input"))
    )
    (net (code "44") (name "CLK") (class "Default")
      (node (ref "IC1") (pin "1") (pinfunction "A_1") (pintype "input"))
      (node (ref "JP1") (pin "2") (pinfunction "2_2") (pintype "passive"))
    )
    (net (code "45") (name "CLK_C") (class "Default")
      (node (ref "IC17") (pin "1") (pinfunction "A_1") (pintype "input"))
      (node (ref "IC30") (pin "4") (pinfunction "O_4") (pintype "output"))
    )
    (net (code "46") (name "CLK_D") (class "Default")
      (node (ref "IC31") (pin "4") (pinfunction "O_4") (pintype "output"))
      (node (ref "IC9") (pin "1") (pinfunction "A_1") (pintype "input"))
    )
    (net (code "47") (name "CONT_MODE") (class "Default")
      (node (ref "IC29") (pin "2") (pinfunction "1Q1_2") (pintype "tri_state"))
      (node (ref "IC32") (pin "2") (pinfunction "I1_2") (pintype "input"))
      (node (ref "IC43") (pin "2") (pinfunction "I_2") (pintype "input"))
    )
    (net (code "48") (name "D1") (class "Default")
      (node (ref "IC11") (pin "3") (pinfunction "Q0_3") (pintype "input"))
      (node (ref "IC14") (pin "2") (pinfunction "1Q1_2") (pintype "tri_state"))
    )
    (net (code "49") (name "D2") (class "Default")
      (node (ref "IC11") (pin "5") (pinfunction "Q1_5") (pintype "input"))
      (node (ref "IC14") (pin "3") (pinfunction "1Q2_3") (pintype "tri_state"))
    )
    (net (code "50") (name "D3") (class "Default")
      (node (ref "IC11") (pin "7") (pinfunction "Q2_7") (pintype "input"))
      (node (ref "IC14") (pin "5") (pinfunction "1Q3_5") (pintype "tri_state"))
    )
    (net (code "51") (name "D4") (class "Default")
      (node (ref "IC11") (pin "9") (pinfunction "Q3_9") (pintype "input"))
      (node (ref "IC14") (pin "6") (pinfunction "1Q4_6") (pintype "tri_state"))
    )
    (net (code "52") (name "D5") (class "Default")
      (node (ref "IC11") (pin "12") (pinfunction "Q4_12") (pintype "input"))
      (node (ref "IC14") (pin "8") (pinfunction "1Q5_8") (pintype "tri_state"))
    )
    (net (code "53") (name "D6") (class "Default")
      (node (ref "IC11") (pin "14") (pinfunction "Q5_14") (pintype "input"))
      (node (ref "IC14") (pin "9") (pinfunction "1Q6_9") (pintype "tri_state"))
    )
    (net (code "54") (name "D7") (class "Default")
      (node (ref "IC11") (pin "16") (pinfunction "Q6_16") (pintype "input"))
      (node (ref "IC14") (pin "11") (pinfunction "1Q7_11") (pintype "tri_state"))
    )
    (net (code "55") (name "D8") (class "Default")
      (node (ref "IC11") (pin "18") (pinfunction "Q7_18") (pintype "input"))
      (node (ref "IC14") (pin "12") (pinfunction "1Q8_12") (pintype "tri_state"))
    )
    (net (code "56") (name "D9") (class "Default")
      (node (ref "IC12") (pin "3") (pinfunction "Q0_3") (pintype "input"))
      (node (ref "IC14") (pin "13") (pinfunction "2Q1_13") (pintype "tri_state"))
    )
    (net (code "57") (name "D10") (class "Default")
      (node (ref "IC12") (pin "5") (pinfunction "Q1_5") (pintype "input"))
      (node (ref "IC14") (pin "14") (pinfunction "2Q2_14") (pintype "tri_state"))
    )
    (net (code "58") (name "D11") (class "Default")
      (node (ref "IC12") (pin "7") (pinfunction "Q2_7") (pintype "input"))
      (node (ref "IC14") (pin "16") (pinfunction "2Q3_16") (pintype "tri_state"))
    )
    (net (code "59") (name "D12") (class "Default")
      (node (ref "IC12") (pin "9") (pinfunction "Q3_9") (pintype "input"))
      (node (ref "IC14") (pin "17") (pinfunction "2Q4_17") (pintype "tri_state"))
    )
    (net (code "60") (name "D13") (class "Default")
      (node (ref "IC12") (pin "12") (pinfunction "Q4_12") (pintype "input"))
      (node (ref "IC14") (pin "19") (pinfunction "2Q5_19") (pintype "tri_state"))
    )
    (net (code "61") (name "D14") (class "Default")
      (node (ref "IC12") (pin "14") (pinfunction "Q5_14") (pintype "input"))
      (node (ref "IC14") (pin "20") (pinfunction "2Q6_20") (pintype "tri_state"))
    )
    (net (code "62") (name "D15") (class "Default")
      (node (ref "IC12") (pin "16") (pinfunction "Q6_16") (pintype "input"))
      (node (ref "IC14") (pin "22") (pinfunction "2Q7_22") (pintype "tri_state"))
    )
    (net (code "63") (name "D16") (class "Default")
      (node (ref "IC12") (pin "18") (pinfunction "Q7_18") (pintype "input"))
      (node (ref "IC14") (pin "23") (pinfunction "2Q8_23") (pintype "tri_state"))
    )
    (net (code "64") (name "DATA0") (class "Default")
      (node (ref "IC14") (pin "47") (pinfunction "1D1_47") (pintype "input"))
      (node (ref "IC22") (pin "47") (pinfunction "1D1_47") (pintype "input"))
      (node (ref "IC24") (pin "2") (pinfunction "1Y1_2") (pintype "tri_state"))
      (node (ref "IC29") (pin "47") (pinfunction "1D1_47") (pintype "input"))
      (node (ref "IC7") (pin "47") (pinfunction "1D1_47") (pintype "input"))
    )
    (net (code "65") (name "DATA1") (class "Default")
      (node (ref "IC14") (pin "46") (pinfunction "1D2_46") (pintype "input"))
      (node (ref "IC22") (pin "46") (pinfunction "1D2_46") (pintype "input"))
      (node (ref "IC24") (pin "3") (pinfunction "1Y2_3") (pintype "tri_state"))
      (node (ref "IC29") (pin "46") (pinfunction "1D2_46") (pintype "input"))
      (node (ref "IC7") (pin "46") (pinfunction "1D2_46") (pintype "input"))
    )
    (net (code "66") (name "DATA2") (class "Default")
      (node (ref "IC14") (pin "44") (pinfunction "1D3_44") (pintype "input"))
      (node (ref "IC22") (pin "44") (pinfunction "1D3_44") (pintype "input"))
      (node (ref "IC24") (pin "5") (pinfunction "1Y3_5") (pintype "tri_state"))
      (node (ref "IC37") (pin "1") (pinfunction "I0_1") (pintype "input"))
      (node (ref "IC7") (pin "44") (pinfunction "1D3_44") (pintype "input"))
    )
    (net (code "67") (name "DATA3") (class "Default")
      (node (ref "IC14") (pin "43") (pinfunction "1D4_43") (pintype "input"))
      (node (ref "IC22") (pin "43") (pinfunction "1D4_43") (pintype "input"))
      (node (ref "IC24") (pin "6") (pinfunction "1Y4_6") (pintype "tri_state"))
      (node (ref "IC29") (pin "43") (pinfunction "1D4_43") (pintype "input"))
      (node (ref "IC7") (pin "43") (pinfunction "1D4_43") (pintype "input"))
    )
    (net (code "68") (name "DATA4") (class "Default")
      (node (ref "IC14") (pin "41") (pinfunction "1D5_41") (pintype "input"))
      (node (ref "IC22") (pin "41") (pinfunction "1D5_41") (pintype "input"))
      (node (ref "IC24") (pin "8") (pinfunction "2Y1_8") (pintype "tri_state"))
      (node (ref "IC29") (pin "41") (pinfunction "1D5_41") (pintype "input"))
      (node (ref "IC7") (pin "41") (pinfunction "1D5_41") (pintype "input"))
    )
    (net (code "69") (name "DATA5") (class "Default")
      (node (ref "IC14") (pin "40") (pinfunction "1D6_40") (pintype "input"))
      (node (ref "IC22") (pin "40") (pinfunction "1D6_40") (pintype "input"))
      (node (ref "IC24") (pin "9") (pinfunction "2Y2_9") (pintype "tri_state"))
      (node (ref "IC29") (pin "40") (pinfunction "1D6_40") (pintype "input"))
      (node (ref "IC7") (pin "40") (pinfunction "1D6_40") (pintype "input"))
    )
    (net (code "70") (name "DATA6") (class "Default")
      (node (ref "IC14") (pin "38") (pinfunction "1D7_38") (pintype "input"))
      (node (ref "IC22") (pin "38") (pinfunction "1D7_38") (pintype "input"))
      (node (ref "IC24") (pin "11") (pinfunction "2Y3_11") (pintype "tri_state"))
      (node (ref "IC29") (pin "38") (pinfunction "1D7_38") (pintype "input"))
      (node (ref "IC7") (pin "38") (pinfunction "1D7_38") (pintype "input"))
    )
    (net (code "71") (name "DATA7") (class "Default")
      (node (ref "IC14") (pin "37") (pinfunction "1D8_37") (pintype "input"))
      (node (ref "IC22") (pin "37") (pinfunction "1D8_37") (pintype "input"))
      (node (ref "IC24") (pin "12") (pinfunction "2Y4_12") (pintype "tri_state"))
      (node (ref "IC29") (pin "37") (pinfunction "1D8_37") (pintype "input"))
      (node (ref "IC7") (pin "37") (pinfunction "1D8_37") (pintype "input"))
    )
    (net (code "72") (name "DATA8") (class "Default")
      (node (ref "IC14") (pin "36") (pinfunction "2D1_36") (pintype "input"))
      (node (ref "IC22") (pin "36") (pinfunction "2D1_36") (pintype "input"))
      (node (ref "IC24") (pin "13") (pinfunction "3Y1_13") (pintype "tri_state"))
      (node (ref "IC29") (pin "36") (pinfunction "2D1_36") (pintype "input"))
      (node (ref "IC7") (pin "36") (pinfunction "2D1_36") (pintype "input"))
    )
    (net (code "73") (name "DATA9") (class "Default")
      (node (ref "IC14") (pin "35") (pinfunction "2D2_35") (pintype "input"))
      (node (ref "IC22") (pin "35") (pinfunction "2D2_35") (pintype "input"))
      (node (ref "IC24") (pin "14") (pinfunction "3Y2_14") (pintype "tri_state"))
      (node (ref "IC29") (pin "35") (pinfunction "2D2_35") (pintype "input"))
      (node (ref "IC7") (pin "35") (pinfunction "2D2_35") (pintype "input"))
    )
    (net (code "74") (name "DATA10") (class "Default")
      (node (ref "IC14") (pin "33") (pinfunction "2D3_33") (pintype "input"))
      (node (ref "IC22") (pin "33") (pinfunction "2D3_33") (pintype "input"))
      (node (ref "IC24") (pin "16") (pinfunction "3Y3_16") (pintype "tri_state"))
      (node (ref "IC29") (pin "33") (pinfunction "2D3_33") (pintype "input"))
      (node (ref "IC7") (pin "33") (pinfunction "2D3_33") (pintype "input"))
    )
    (net (code "75") (name "DATA11") (class "Default")
      (node (ref "IC14") (pin "32") (pinfunction "2D4_32") (pintype "input"))
      (node (ref "IC22") (pin "32") (pinfunction "2D4_32") (pintype "input"))
      (node (ref "IC24") (pin "17") (pinfunction "3Y4_17") (pintype "tri_state"))
      (node (ref "IC29") (pin "32") (pinfunction "2D4_32") (pintype "input"))
      (node (ref "IC7") (pin "32") (pinfunction "2D4_32") (pintype "input"))
    )
    (net (code "76") (name "DATA12") (class "Default")
      (node (ref "IC14") (pin "30") (pinfunction "2D5_30") (pintype "input"))
      (node (ref "IC22") (pin "30") (pinfunction "2D5_30") (pintype "input"))
      (node (ref "IC24") (pin "19") (pinfunction "4Y1_19") (pintype "tri_state"))
      (node (ref "IC29") (pin "30") (pinfunction "2D5_30") (pintype "input"))
      (node (ref "IC7") (pin "30") (pinfunction "2D5_30") (pintype "input"))
    )
    (net (code "77") (name "DATA13") (class "Default")
      (node (ref "IC14") (pin "29") (pinfunction "2D6_29") (pintype "input"))
      (node (ref "IC22") (pin "29") (pinfunction "2D6_29") (pintype "input"))
      (node (ref "IC24") (pin "20") (pinfunction "4Y2_20") (pintype "tri_state"))
      (node (ref "IC29") (pin "29") (pinfunction "2D6_29") (pintype "input"))
      (node (ref "IC7") (pin "29") (pinfunction "2D6_29") (pintype "input"))
    )
    (net (code "78") (name "DATA14") (class "Default")
      (node (ref "IC14") (pin "27") (pinfunction "2D7_27") (pintype "input"))
      (node (ref "IC22") (pin "27") (pinfunction "2D7_27") (pintype "input"))
      (node (ref "IC24") (pin "22") (pinfunction "4Y3_22") (pintype "tri_state"))
      (node (ref "IC29") (pin "27") (pinfunction "2D7_27") (pintype "input"))
      (node (ref "IC7") (pin "27") (pinfunction "2D7_27") (pintype "input"))
    )
    (net (code "79") (name "DATA15") (class "Default")
      (node (ref "IC14") (pin "26") (pinfunction "2D8_26") (pintype "input"))
      (node (ref "IC22") (pin "26") (pinfunction "2D8_26") (pintype "input"))
      (node (ref "IC24") (pin "23") (pinfunction "4Y4_23") (pintype "tri_state"))
      (node (ref "IC29") (pin "26") (pinfunction "2D8_26") (pintype "input"))
      (node (ref "IC7") (pin "26") (pinfunction "2D8_26") (pintype "input"))
    )
    (net (code "80") (name "ENABLE") (class "Default")
      (node (ref "IC25") (pin "23") (pinfunction "4Y4_23") (pintype "tri_state"))
      (node (ref "IC46") (pin "1") (pinfunction "I0_1") (pintype "input"))
    )
    (net (code "81") (name "GND") (class "Default")
      (node (ref "C1") (pin "2") (pinfunction "2_2") (pintype "passive"))
      (node (ref "C10") (pin "2") (pinfunction "2_2") (pintype "passive"))
      (node (ref "C11") (pin "2") (pinfunction "2_2") (pintype "passive"))
      (node (ref "C12") (pin "2") (pinfunction "2_2") (pintype "passive"))
      (node (ref "C13") (pin "2") (pinfunction "2_2") (pintype "passive"))
      (node (ref "C14") (pin "2") (pinfunction "2_2") (pintype "passive"))
      (node (ref "C15") (pin "2") (pinfunction "2_2") (pintype "passive"))
      (node (ref "C16") (pin "2") (pinfunction "2_2") (pintype "passive"))
      (node (ref "C17") (pin "2") (pinfunction "2_2") (pintype "passive"))
      (node (ref "C18") (pin "2") (pinfunction "2_2") (pintype "passive"))
      (node (ref "C19") (pin "2") (pinfunction "2_2") (pintype "passive"))
      (node (ref "C2") (pin "2") (pinfunction "2_2") (pintype "passive"))
      (node (ref "C20") (pin "2") (pinfunction "2_2") (pintype "passive"))
      (node (ref "C21") (pin "2") (pinfunction "2_2") (pintype "passive"))
      (node (ref "C22") (pin "2") (pinfunction "2_2") (pintype "passive"))
      (node (ref "C23") (pin "2") (pinfunction "2_2") (pintype "passive"))
      (node (ref "C24") (pin "2") (pinfunction "2_2") (pintype "passive"))
      (node (ref "C25") (pin "2") (pinfunction "2_2") (pintype "passive"))
      (node (ref "C26") (pin "2") (pinfunction "2_2") (pintype "passive"))
      (node (ref "C27") (pin "2") (pinfunction "2_2") (pintype "passive"))
      (node (ref "C28") (pin "2") (pinfunction "2_2") (pintype "passive"))
      (node (ref "C29") (pin "2") (pinfunction "2_2") (pintype "passive"))
      (node (ref "C3") (pin "2") (pinfunction "2_2") (pintype "passive"))
      (node (ref "C4") (pin "2") (pinfunction "2_2") (pintype "passive"))
      (node (ref "C5") (pin "2") (pinfunction "2_2") (pintype "passive"))
      (node (ref "C6") (pin "2") (pinfunction "2_2") (pintype "passive"))
      (node (ref "C7") (pin "2") (pinfunction "2_2") (pintype "passive"))
      (node (ref "C8") (pin "2") (pinfunction "2_2") (pintype "passive"))
      (node (ref "C9") (pin "2") (pinfunction "2_2") (pintype "passive"))
      (node (ref "IC11") (pin "1") (pinfunction "G_1") (pintype "input"))
      (node (ref "IC12") (pin "1") (pinfunction "G_1") (pintype "input"))
      (node (ref "IC14") (pin "1") (pinfunction "1OE_1") (pintype "input"))
      (node (ref "IC14") (pin "24") (pinfunction "2OE_24") (pintype "input"))
      (node (ref "IC16") (pin "1") (pinfunction "G_1") (pintype "input"))
      (node (ref "IC19") (pin "1") (pinfunction "G_1") (pintype "input"))
      (node (ref "IC20") (pin "1") (pinfunction "G_1") (pintype "input"))
      (node (ref "IC22") (pin "1") (pinfunction "1OE_1") (pintype "input"))
      (node (ref "IC22") (pin "24") (pinfunction "2OE_24") (pintype "input"))
      (node (ref "IC24") (pin "1") (pinfunction "1G_1") (pintype "input"))
      (node (ref "IC24") (pin "24") (pinfunction "4G_24") (pintype "input"))
      (node (ref "IC24") (pin "25") (pinfunction "3G_25") (pintype "input"))
      (node (ref "IC24") (pin "48") (pinfunction "2G_48") (pintype "input"))
      (node (ref "IC25") (pin "1") (pinfunction "1G_1") (pintype "input"))
      (node (ref "IC25") (pin "24") (pinfunction "4G_24") (pintype "input"))
      (node (ref "IC25") (pin "25") (pinfunction "3G_25") (pintype "input"))
      (node (ref "IC25") (pin "48") (pinfunction "2G_48") (pintype "input"))
      (node (ref "IC29") (pin "1") (pinfunction "1OE_1") (pintype "input"))
      (node (ref "IC29") (pin "24") (pinfunction "2OE_24") (pintype "input"))
      (node (ref "IC4") (pin "1") (pinfunction "G_1") (pintype "input"))
      (node (ref "IC5") (pin "1") (pinfunction "G_1") (pintype "input"))
      (node (ref "IC7") (pin "1") (pinfunction "1OE_1") (pintype "input"))
      (node (ref "IC7") (pin "24") (pinfunction "2OE_24") (pintype "input"))
      (node (ref "J1") (pin "A10") (pinfunction "A10_A10") (pintype "passive"))
      (node (ref "J1") (pin "A11") (pinfunction "A11_A11") (pintype "passive"))
      (node (ref "J1") (pin "A12") (pinfunction "A12_A12") (pintype "passive"))
      (node (ref "J1") (pin "A13") (pinfunction "A13_A13") (pintype "passive"))
      (node (ref "J1") (pin "A14") (pinfunction "A14_A14") (pintype "passive"))
      (node (ref "J1") (pin "A15") (pinfunction "A15_A15") (pintype "passive"))
      (node (ref "J1") (pin "A16") (pinfunction "A16_A16") (pintype "passive"))
      (node (ref "J1") (pin "A17") (pinfunction "A17_A17") (pintype "passive"))
      (node (ref "J1") (pin "A18") (pinfunction "A18_A18") (pintype "passive"))
      (node (ref "J1") (pin "A19") (pinfunction "A19_A19") (pintype "passive"))
      (node (ref "J1") (pin "A20") (pinfunction "A20_A20") (pintype "passive"))
      (node (ref "J1") (pin "A21") (pinfunction "A21_A21") (pintype "passive"))
      (node (ref "J1") (pin "A22") (pinfunction "A22_A22") (pintype "passive"))
      (node (ref "J1") (pin "A23") (pinfunction "A23_A23") (pintype "passive"))
      (node (ref "J1") (pin "A24") (pinfunction "A24_A24") (pintype "passive"))
      (node (ref "J1") (pin "A9") (pinfunction "A9_A9") (pintype "passive"))
      (node (ref "LED1") (pin "K") (pinfunction "C_K") (pintype "passive"))
      (node (ref "LED2") (pin "K") (pinfunction "C_K") (pintype "passive"))
      (node (ref "LED3") (pin "K") (pinfunction "C_K") (pintype "passive"))
      (node (ref "Q1") (pin "2") (pinfunction "GND_2") (pintype "power_in"))
      (node (ref "R19") (pin "1") (pinfunction "1_1") (pintype "passive"))
      (node (ref "R20") (pin "1") (pinfunction "1_1") (pintype "passive"))
      (node (ref "R21") (pin "1") (pinfunction "1_1") (pintype "passive"))
      (node (ref "R22") (pin "1") (pinfunction "1_1") (pintype "passive"))
      (node (ref "R23") (pin "1") (pinfunction "1_1") (pintype "passive"))
      (node (ref "R24") (pin "1") (pinfunction "1_1") (pintype "passive"))
      (node (ref "R25") (pin "1") (pinfunction "1_1") (pintype "passive"))
      (node (ref "R26") (pin "1") (pinfunction "1_1") (pintype "passive"))
      (node (ref "U$1") (pin "1") (pinfunction "CLK_1") (pintype "input"))
      (node (ref "U$1") (pin "2") (pinfunction "D_2") (pintype "input"))
      (node (ref "U$3") (pin "2") (pinfunction "GND_2") (pintype "passive"))
      (node (ref "U$3") (pin "3") (pinfunction "GND_3") (pintype "passive"))
      (node (ref "U$3") (pin "4") (pinfunction "GND_4") (pintype "passive"))
      (node (ref "U$3") (pin "5") (pinfunction "GND_5") (pintype "passive"))
      (node (ref "U$9") (pin "1") (pinfunction "GND_1") (pintype "bidirectional"))
    )
    (net (code "82") (name "GND{slash}NC") (class "Default")
      (node (ref "Q1") (pin "1") (pinfunction "GND/NC_1") (pintype "power_in"))
    )
    (net (code "83") (name "IS_EQUAL_B") (class "Default")
      (node (ref "IC1") (pin "12") (pinfunction "CLR_12") (pintype "input"))
      (node (ref "IC1") (pin "2") (pinfunction "CLR_2") (pintype "input"))
      (node (ref "IC3") (pin "12") (pinfunction "CLR_12") (pintype "input"))
      (node (ref "IC3") (pin "2") (pinfunction "CLR_2") (pintype "input"))
      (node (ref "IC45") (pin "2") (pinfunction "I_2") (pintype "input"))
      (node (ref "IC6") (pin "4") (pinfunction "O_4") (pintype "output"))
      (node (ref "IC8") (pin "1") (pinfunction "I0_1") (pintype "input"))
    )
    (net (code "84") (name "IS_EQUAL_C") (class "Default")
      (node (ref "IC21") (pin "4") (pinfunction "O_4") (pintype "output"))
      (node (ref "IC23") (pin "2") (pinfunction "I1_2") (pintype "input"))
      (node (ref "IC27") (pin "11") (pinfunction "I_11") (pintype "input"))
      (node (ref "IC33") (pin "1") (pinfunction "I0_1") (pintype "input"))
    )
    (net (code "85") (name "IS_EQUAL_D") (class "Default")
      (node (ref "IC13") (pin "4") (pinfunction "O_4") (pintype "output"))
      (node (ref "IC15") (pin "2") (pinfunction "I1_2") (pintype "input"))
      (node (ref "IC27") (pin "9") (pinfunction "I_9") (pintype "input"))
    )
    (net (code "86") (name "IS_SEL") (class "Default")
      (node (ref "IC27") (pin "6") (pinfunction "O_6") (pintype "output"))
      (node (ref "IC28") (pin "2") (pinfunction "I1_2") (pintype "input"))
      (node (ref "IC41") (pin "2") (pinfunction "I_2") (pintype "input"))
    )
    (net (code "87") (name "MOD_CLK_TIMING") (class "Default")
      (node (ref "IC8") (pin "4") (pinfunction "O_4") (pintype "output"))
      (node (ref "J1") (pin "A28") (pinfunction "A28_A28") (pintype "passive"))
    )
    (net (code "88") (name "MOD_RESET") (class "Default")
      (node (ref "IC33") (pin "4") (pinfunction "O_4") (pintype "output"))
      (node (ref "J1") (pin "A27") (pinfunction "A27_A27") (pintype "passive"))
    )
    (net (code "89") (name "MOD_RES_SEL") (class "Default")
      (node (ref "IC29") (pin "3") (pinfunction "1Q2_3") (pintype "tri_state"))
      (node (ref "IC33") (pin "2") (pinfunction "I1_2") (pintype "input"))
    )
    (net (code "90") (name "Net-(IC1A-QA)") (class "Default")
      (node (ref "IC1") (pin "3") (pinfunction "QA_3") (pintype "output"))
      (node (ref "IC4") (pin "2") (pinfunction "P0_2") (pintype "input"))
    )
    (net (code "91") (name "Net-(IC1A-QB)") (class "Default")
      (node (ref "IC1") (pin "4") (pinfunction "QB_4") (pintype "output"))
      (node (ref "IC4") (pin "4") (pinfunction "P1_4") (pintype "input"))
    )
    (net (code "92") (name "Net-(IC1A-QC)") (class "Default")
      (node (ref "IC1") (pin "5") (pinfunction "QC_5") (pintype "output"))
      (node (ref "IC4") (pin "6") (pinfunction "P2_6") (pintype "input"))
    )
    (net (code "93") (name "Net-(IC1A-QD)") (class "Default")
      (node (ref "IC1") (pin "13") (pinfunction "A_13") (pintype "input"))
      (node (ref "IC1") (pin "6") (pinfunction "QD_6") (pintype "output"))
      (node (ref "IC4") (pin "8") (pinfunction "P3_8") (pintype "input"))
    )
    (net (code "94") (name "Net-(IC1B-QA)") (class "Default")
      (node (ref "IC1") (pin "11") (pinfunction "QA_11") (pintype "output"))
      (node (ref "IC4") (pin "11") (pinfunction "P4_11") (pintype "input"))
    )
    (net (code "95") (name "Net-(IC1B-QB)") (class "Default")
      (node (ref "IC1") (pin "10") (pinfunction "QB_10") (pintype "output"))
      (node (ref "IC4") (pin "13") (pinfunction "P5_13") (pintype "input"))
    )
    (net (code "96") (name "Net-(IC1B-QC)") (class "Default")
      (node (ref "IC1") (pin "9") (pinfunction "QC_9") (pintype "output"))
      (node (ref "IC4") (pin "15") (pinfunction "P6_15") (pintype "input"))
    )
    (net (code "97") (name "Net-(IC1B-QD)") (class "Default")
      (node (ref "IC1") (pin "8") (pinfunction "QD_8") (pintype "output"))
      (node (ref "IC3") (pin "1") (pinfunction "A_1") (pintype "input"))
      (node (ref "IC4") (pin "17") (pinfunction "P7_17") (pintype "input"))
    )
    (net (code "98") (name "Net-(IC3A-QA)") (class "Default")
      (node (ref "IC3") (pin "3") (pinfunction "QA_3") (pintype "output"))
      (node (ref "IC5") (pin "2") (pinfunction "P0_2") (pintype "input"))
    )
    (net (code "99") (name "Net-(IC3A-QB)") (class "Default")
      (node (ref "IC3") (pin "4") (pinfunction "QB_4") (pintype "output"))
      (node (ref "IC5") (pin "4") (pinfunction "P1_4") (pintype "input"))
    )
    (net (code "100") (name "Net-(IC3A-QC)") (class "Default")
      (node (ref "IC3") (pin "5") (pinfunction "QC_5") (pintype "output"))
      (node (ref "IC5") (pin "6") (pinfunction "P2_6") (pintype "input"))
    )
    (net (code "101") (name "Net-(IC3A-QD)") (class "Default")
      (node (ref "IC3") (pin "13") (pinfunction "A_13") (pintype "input"))
      (node (ref "IC3") (pin "6") (pinfunction "QD_6") (pintype "output"))
      (node (ref "IC5") (pin "8") (pinfunction "P3_8") (pintype "input"))
    )
    (net (code "102") (name "Net-(IC3B-QA)") (class "Default")
      (node (ref "IC3") (pin "11") (pinfunction "QA_11") (pintype "output"))
      (node (ref "IC5") (pin "11") (pinfunction "P4_11") (pintype "input"))
    )
    (net (code "103") (name "Net-(IC3B-QB)") (class "Default")
      (node (ref "IC3") (pin "10") (pinfunction "QB_10") (pintype "output"))
      (node (ref "IC5") (pin "13") (pinfunction "P5_13") (pintype "input"))
    )
    (net (code "104") (name "Net-(IC3B-QC)") (class "Default")
      (node (ref "IC3") (pin "9") (pinfunction "QC_9") (pintype "output"))
      (node (ref "IC5") (pin "15") (pinfunction "P6_15") (pintype "input"))
    )
    (net (code "105") (name "Net-(IC3B-QD)") (class "Default")
      (node (ref "IC3") (pin "8") (pinfunction "QD_8") (pintype "output"))
      (node (ref "IC5") (pin "17") (pinfunction "P7_17") (pintype "input"))
    )
    (net (code "106") (name "Net-(IC4A-P=Q)") (class "Default")
      (node (ref "IC4") (pin "19") (pinfunction "P=Q_19") (pintype "output"))
      (node (ref "IC6") (pin "1") (pinfunction "I0_1") (pintype "input"))
    )
    (net (code "107") (name "Net-(IC5A-P=Q)") (class "Default")
      (node (ref "IC5") (pin "19") (pinfunction "P=Q_19") (pintype "output"))
      (node (ref "IC6") (pin "2") (pinfunction "I1_2") (pintype "input"))
    )
    (net (code "108") (name "Net-(IC10A-A)") (class "Default")
      (node (ref "IC10") (pin "1") (pinfunction "A_1") (pintype "input"))
      (node (ref "IC11") (pin "17") (pinfunction "P7_17") (pintype "input"))
      (node (ref "IC9") (pin "8") (pinfunction "QD_8") (pintype "output"))
    )
    (net (code "109") (name "Net-(IC10A-CLR)") (class "Default")
      (node (ref "IC10") (pin "12") (pinfunction "CLR_12") (pintype "input"))
      (node (ref "IC10") (pin "2") (pinfunction "CLR_2") (pintype "input"))
      (node (ref "IC15") (pin "4") (pinfunction "O_4") (pintype "output"))
      (node (ref "IC9") (pin "12") (pinfunction "CLR_12") (pintype "input"))
      (node (ref "IC9") (pin "2") (pinfunction "CLR_2") (pintype "input"))
    )
    (net (code "110") (name "Net-(IC10A-QA)") (class "Default")
      (node (ref "IC10") (pin "3") (pinfunction "QA_3") (pintype "output"))
      (node (ref "IC12") (pin "2") (pinfunction "P0_2") (pintype "input"))
    )
    (net (code "111") (name "Net-(IC10A-QB)") (class "Default")
      (node (ref "IC10") (pin "4") (pinfunction "QB_4") (pintype "output"))
      (node (ref "IC12") (pin "4") (pinfunction "P1_4") (pintype "input"))
    )
    (net (code "112") (name "Net-(IC10A-QC)") (class "Default")
      (node (ref "IC10") (pin "5") (pinfunction "QC_5") (pintype "output"))
      (node (ref "IC12") (pin "6") (pinfunction "P2_6") (pintype "input"))
    )
    (net (code "113") (name "Net-(IC10A-QD)") (class "Default")
      (node (ref "IC10") (pin "13") (pinfunction "A_13") (pintype "input"))
      (node (ref "IC10") (pin "6") (pinfunction "QD_6") (pintype "output"))
      (node (ref "IC12") (pin "8") (pinfunction "P3_8") (pintype "input"))
    )
    (net (code "114") (name "Net-(IC10B-QA)") (class "Default")
      (node (ref "IC10") (pin "11") (pinfunction "QA_11") (pintype "output"))
      (node (ref "IC12") (pin "11") (pinfunction "P4_11") (pintype "input"))
    )
    (net (code "115") (name "Net-(IC10B-QB)") (class "Default")
      (node (ref "IC10") (pin "10") (pinfunction "QB_10") (pintype "output"))
      (node (ref "IC12") (pin "13") (pinfunction "P5_13") (pintype "input"))
    )
    (net (code "116") (name "Net-(IC10B-QC)") (class "Default")
      (node (ref "IC10") (pin "9") (pinfunction "QC_9") (pintype "output"))
      (node (ref "IC12") (pin "15") (pinfunction "P6_15") (pintype "input"))
    )
    (net (code "117") (name "Net-(IC10B-QD)") (class "Default")
      (node (ref "IC10") (pin "8") (pinfunction "QD_8") (pintype "output"))
      (node (ref "IC12") (pin "17") (pinfunction "P7_17") (pintype "input"))
    )
    (net (code "118") (name "Net-(IC11A-P0)") (class "Default")
      (node (ref "IC11") (pin "2") (pinfunction "P0_2") (pintype "input"))
      (node (ref "IC9") (pin "3") (pinfunction "QA_3") (pintype "output"))
    )
    (net (code "119") (name "Net-(IC11A-P1)") (class "Default")
      (node (ref "IC11") (pin "4") (pinfunction "P1_4") (pintype "input"))
      (node (ref "IC9") (pin "4") (pinfunction "QB_4") (pintype "output"))
    )
    (net (code "120") (name "Net-(IC11A-P2)") (class "Default")
      (node (ref "IC11") (pin "6") (pinfunction "P2_6") (pintype "input"))
      (node (ref "IC9") (pin "5") (pinfunction "QC_5") (pintype "output"))
    )
    (net (code "121") (name "Net-(IC11A-P3)") (class "Default")
      (node (ref "IC11") (pin "8") (pinfunction "P3_8") (pintype "input"))
      (node (ref "IC9") (pin "13") (pinfunction "A_13") (pintype "input"))
      (node (ref "IC9") (pin "6") (pinfunction "QD_6") (pintype "output"))
    )
    (net (code "122") (name "Net-(IC11A-P4)") (class "Default")
      (node (ref "IC11") (pin "11") (pinfunction "P4_11") (pintype "input"))
      (node (ref "IC9") (pin "11") (pinfunction "QA_11") (pintype "output"))
    )
    (net (code "123") (name "Net-(IC11A-P5)") (class "Default")
      (node (ref "IC11") (pin "13") (pinfunction "P5_13") (pintype "input"))
      (node (ref "IC9") (pin "10") (pinfunction "QB_10") (pintype "output"))
    )
    (net (code "124") (name "Net-(IC11A-P6)") (class "Default")
      (node (ref "IC11") (pin "15") (pinfunction "P6_15") (pintype "input"))
      (node (ref "IC9") (pin "9") (pinfunction "QC_9") (pintype "output"))
    )
    (net (code "125") (name "Net-(IC11A-P=Q)") (class "Default")
      (node (ref "IC11") (pin "19") (pinfunction "P=Q_19") (pintype "output"))
      (node (ref "IC13") (pin "1") (pinfunction "I0_1") (pintype "input"))
    )
    (net (code "126") (name "Net-(IC12A-P=Q)") (class "Default")
      (node (ref "IC12") (pin "19") (pinfunction "P=Q_19") (pintype "output"))
      (node (ref "IC13") (pin "2") (pinfunction "I1_2") (pintype "input"))
    )
    (net (code "127") (name "Net-(IC16A-P=Q)") (class "Default")
      (node (ref "IC16") (pin "19") (pinfunction "P=Q_19") (pintype "output"))
      (node (ref "IC27") (pin "5") (pinfunction "I_5") (pintype "input"))
    )
    (net (code "128") (name "Net-(IC16A-Q0)") (class "Default")
      (node (ref "IC16") (pin "3") (pinfunction "Q0_3") (pintype "input"))
      (node (ref "R19") (pin "2") (pinfunction "2_2") (pintype "passive"))
      (node (ref "S1") (pin "16") (pinfunction "16_16") (pintype "passive"))
    )
    (net (code "129") (name "Net-(IC16A-Q1)") (class "Default")
      (node (ref "IC16") (pin "5") (pinfunction "Q1_5") (pintype "input"))
      (node (ref "R20") (pin "2") (pinfunction "2_2") (pintype "passive"))
      (node (ref "S1") (pin "15") (pinfunction "15_15") (pintype "passive"))
    )
    (net (code "130") (name "Net-(IC16A-Q2)") (class "Default")
      (node (ref "IC16") (pin "7") (pinfunction "Q2_7") (pintype "input"))
      (node (ref "R21") (pin "2") (pinfunction "2_2") (pintype "passive"))
      (node (ref "S1") (pin "14") (pinfunction "14_14") (pintype "passive"))
    )
    (net (code "131") (name "Net-(IC16A-Q3)") (class "Default")
      (node (ref "IC16") (pin "9") (pinfunction "Q3_9") (pintype "input"))
      (node (ref "R22") (pin "2") (pinfunction "2_2") (pintype "passive"))
      (node (ref "S1") (pin "13") (pinfunction "13_13") (pintype "passive"))
    )
    (net (code "132") (name "Net-(IC16A-Q4)") (class "Default")
      (node (ref "IC16") (pin "12") (pinfunction "Q4_12") (pintype "input"))
      (node (ref "R23") (pin "2") (pinfunction "2_2") (pintype "passive"))
      (node (ref "S1") (pin "12") (pinfunction "12_12") (pintype "passive"))
    )
    (net (code "133") (name "Net-(IC16A-Q5)") (class "Default")
      (node (ref "IC16") (pin "14") (pinfunction "Q5_14") (pintype "input"))
      (node (ref "R24") (pin "2") (pinfunction "2_2") (pintype "passive"))
      (node (ref "S1") (pin "11") (pinfunction "11_11") (pintype "passive"))
    )
    (net (code "134") (name "Net-(IC16A-Q6)") (class "Default")
      (node (ref "IC16") (pin "16") (pinfunction "Q6_16") (pintype "input"))
      (node (ref "R25") (pin "2") (pinfunction "2_2") (pintype "passive"))
      (node (ref "S1") (pin "10") (pinfunction "10_10") (pintype "passive"))
    )
    (net (code "135") (name "Net-(IC16A-Q7)") (class "Default")
      (node (ref "IC16") (pin "18") (pinfunction "Q7_18") (pintype "input"))
      (node (ref "R26") (pin "2") (pinfunction "2_2") (pintype "passive"))
      (node (ref "S1") (pin "9") (pinfunction "9_9") (pintype "passive"))
    )
    (net (code "136") (name "Net-(IC17A-CLR)") (class "Default")
      (node (ref "IC17") (pin "12") (pinfunction "CLR_12") (pintype "input"))
      (node (ref "IC17") (pin "2") (pinfunction "CLR_2") (pintype "input"))
      (node (ref "IC18") (pin "12") (pinfunction "CLR_12") (pintype "input"))
      (node (ref "IC18") (pin "2") (pinfunction "CLR_2") (pintype "input"))
      (node (ref "IC23") (pin "4") (pinfunction "O_4") (pintype "output"))
    )
    (net (code "137") (name "Net-(IC17A-QA)") (class "Default")
      (node (ref "IC17") (pin "3") (pinfunction "QA_3") (pintype "output"))
      (node (ref "IC19") (pin "2") (pinfunction "P0_2") (pintype "input"))
    )
    (net (code "138") (name "Net-(IC17A-QB)") (class "Default")
      (node (ref "IC17") (pin "4") (pinfunction "QB_4") (pintype "output"))
      (node (ref "IC19") (pin "4") (pinfunction "P1_4") (pintype "input"))
    )
    (net (code "139") (name "Net-(IC17A-QC)") (class "Default")
      (node (ref "IC17") (pin "5") (pinfunction "QC_5") (pintype "output"))
      (node (ref "IC19") (pin "6") (pinfunction "P2_6") (pintype "input"))
    )
    (net (code "140") (name "Net-(IC17A-QD)") (class "Default")
      (node (ref "IC17") (pin "13") (pinfunction "A_13") (pintype "input"))
      (node (ref "IC17") (pin "6") (pinfunction "QD_6") (pintype "output"))
      (node (ref "IC19") (pin "8") (pinfunction "P3_8") (pintype "input"))
    )
    (net (code "141") (name "Net-(IC17B-QA)") (class "Default")
      (node (ref "IC17") (pin "11") (pinfunction "QA_11") (pintype "output"))
      (node (ref "IC19") (pin "11") (pinfunction "P4_11") (pintype "input"))
    )
    (net (code "142") (name "Net-(IC17B-QB)") (class "Default")
      (node (ref "IC17") (pin "10") (pinfunction "QB_10") (pintype "output"))
      (node (ref "IC19") (pin "13") (pinfunction "P5_13") (pintype "input"))
    )
    (net (code "143") (name "Net-(IC17B-QC)") (class "Default")
      (node (ref "IC17") (pin "9") (pinfunction "QC_9") (pintype "output"))
      (node (ref "IC19") (pin "15") (pinfunction "P6_15") (pintype "input"))
    )
    (net (code "144") (name "Net-(IC17B-QD)") (class "Default")
      (node (ref "IC17") (pin "8") (pinfunction "QD_8") (pintype "output"))
      (node (ref "IC18") (pin "1") (pinfunction "A_1") (pintype "input"))
      (node (ref "IC19") (pin "17") (pinfunction "P7_17") (pintype "input"))
    )
    (net (code "145") (name "Net-(IC18A-QA)") (class "Default")
      (node (ref "IC18") (pin "3") (pinfunction "QA_3") (pintype "output"))
      (node (ref "IC20") (pin "2") (pinfunction "P0_2") (pintype "input"))
    )
    (net (code "146") (name "Net-(IC18A-QB)") (class "Default")
      (node (ref "IC18") (pin "4") (pinfunction "QB_4") (pintype "output"))
      (node (ref "IC20") (pin "4") (pinfunction "P1_4") (pintype "input"))
    )
    (net (code "147") (name "Net-(IC18A-QC)") (class "Default")
      (node (ref "IC18") (pin "5") (pinfunction "QC_5") (pintype "output"))
      (node (ref "IC20") (pin "6") (pinfunction "P2_6") (pintype "input"))
    )
    (net (code "148") (name "Net-(IC18A-QD)") (class "Default")
      (node (ref "IC18") (pin "13") (pinfunction "A_13") (pintype "input"))
      (node (ref "IC18") (pin "6") (pinfunction "QD_6") (pintype "output"))
      (node (ref "IC20") (pin "8") (pinfunction "P3_8") (pintype "input"))
    )
    (net (code "149") (name "Net-(IC18B-QA)") (class "Default")
      (node (ref "IC18") (pin "11") (pinfunction "QA_11") (pintype "output"))
      (node (ref "IC20") (pin "11") (pinfunction "P4_11") (pintype "input"))
    )
    (net (code "150") (name "Net-(IC18B-QB)") (class "Default")
      (node (ref "IC18") (pin "10") (pinfunction "QB_10") (pintype "output"))
      (node (ref "IC20") (pin "13") (pinfunction "P5_13") (pintype "input"))
    )
    (net (code "151") (name "Net-(IC18B-QC)") (class "Default")
      (node (ref "IC18") (pin "9") (pinfunction "QC_9") (pintype "output"))
      (node (ref "IC20") (pin "15") (pinfunction "P6_15") (pintype "input"))
    )
    (net (code "152") (name "Net-(IC18B-QD)") (class "Default")
      (node (ref "IC18") (pin "8") (pinfunction "QD_8") (pintype "output"))
      (node (ref "IC20") (pin "17") (pinfunction "P7_17") (pintype "input"))
    )
    (net (code "153") (name "Net-(IC19A-P=Q)") (class "Default")
      (node (ref "IC19") (pin "19") (pinfunction "P=Q_19") (pintype "output"))
      (node (ref "IC21") (pin "1") (pinfunction "I0_1") (pintype "input"))
    )
    (net (code "154") (name "Net-(IC20A-P=Q)") (class "Default")
      (node (ref "IC20") (pin "19") (pinfunction "P=Q_19") (pintype "output"))
      (node (ref "IC21") (pin "2") (pinfunction "I1_2") (pintype "input"))
    )
    (net (code "155") (name "Net-(IC24A-1A1)") (class "Default")
      (node (ref "IC24") (pin "47") (pinfunction "1A1_47") (pintype "input"))
      (node (ref "J1") (pin "C1") (pinfunction "C1_C1") (pintype "passive"))
    )
    (net (code "156") (name "Net-(IC24A-1A2)") (class "Default")
      (node (ref "IC24") (pin "46") (pinfunction "1A2_46") (pintype "input"))
      (node (ref "J1") (pin "C2") (pinfunction "C2_C2") (pintype "passive"))
    )
    (net (code "157") (name "Net-(IC24A-1A3)") (class "Default")
      (node (ref "IC24") (pin "44") (pinfunction "1A3_44") (pintype "input"))
      (node (ref "J1") (pin "C3") (pinfunction "C3_C3") (pintype "passive"))
    )
    (net (code "158") (name "Net-(IC24A-1A4)") (class "Default")
      (node (ref "IC24") (pin "43") (pinfunction "1A4_43") (pintype "input"))
      (node (ref "J1") (pin "C4") (pinfunction "C4_C4") (pintype "passive"))
    )
    (net (code "159") (name "Net-(IC24A-2A1)") (class "Default")
      (node (ref "IC24") (pin "41") (pinfunction "2A1_41") (pintype "input"))
      (node (ref "J1") (pin "C5") (pinfunction "C5_C5") (pintype "passive"))
    )
    (net (code "160") (name "Net-(IC24A-2A2)") (class "Default")
      (node (ref "IC24") (pin "40") (pinfunction "2A2_40") (pintype "input"))
      (node (ref "J1") (pin "C6") (pinfunction "C6_C6") (pintype "passive"))
    )
    (net (code "161") (name "Net-(IC24A-2A3)") (class "Default")
      (node (ref "IC24") (pin "38") (pinfunction "2A3_38") (pintype "input"))
      (node (ref "J1") (pin "C7") (pinfunction "C7_C7") (pintype "passive"))
    )
    (net (code "162") (name "Net-(IC24A-2A4)") (class "Default")
      (node (ref "IC24") (pin "37") (pinfunction "2A4_37") (pintype "input"))
      (node (ref "J1") (pin "C8") (pinfunction "C8_C8") (pintype "passive"))
    )
    (net (code "163") (name "Net-(IC24A-3A1)") (class "Default")
      (node (ref "IC24") (pin "36") (pinfunction "3A1_36") (pintype "input"))
      (node (ref "J1") (pin "C9") (pinfunction "C9_C9") (pintype "passive"))
    )
    (net (code "164") (name "Net-(IC24A-3A2)") (class "Default")
      (node (ref "IC24") (pin "35") (pinfunction "3A2_35") (pintype "input"))
      (node (ref "J1") (pin "C10") (pinfunction "C10_C10") (pintype "passive"))
    )
    (net (code "165") (name "Net-(IC24A-3A3)") (class "Default")
      (node (ref "IC24") (pin "33") (pinfunction "3A3_33") (pintype "input"))
      (node (ref "J1") (pin "C11") (pinfunction "C11_C11") (pintype "passive"))
    )
    (net (code "166") (name "Net-(IC24A-3A4)") (class "Default")
      (node (ref "IC24") (pin "32") (pinfunction "3A4_32") (pintype "input"))
      (node (ref "J1") (pin "C12") (pinfunction "C12_C12") (pintype "passive"))
    )
    (net (code "167") (name "Net-(IC24A-4A1)") (class "Default")
      (node (ref "IC24") (pin "30") (pinfunction "4A1_30") (pintype "input"))
      (node (ref "J1") (pin "C13") (pinfunction "C13_C13") (pintype "passive"))
    )
    (net (code "168") (name "Net-(IC24A-4A2)") (class "Default")
      (node (ref "IC24") (pin "29") (pinfunction "4A2_29") (pintype "input"))
      (node (ref "J1") (pin "C14") (pinfunction "C14_C14") (pintype "passive"))
    )
    (net (code "169") (name "Net-(IC24A-4A3)") (class "Default")
      (node (ref "IC24") (pin "27") (pinfunction "4A3_27") (pintype "input"))
      (node (ref "J1") (pin "C15") (pinfunction "C15_C15") (pintype "passive"))
    )
    (net (code "170") (name "Net-(IC24A-4A4)") (class "Default")
      (node (ref "IC24") (pin "26") (pinfunction "4A4_26") (pintype "input"))
      (node (ref "J1") (pin "C16") (pinfunction "C16_C16") (pintype "passive"))
    )
    (net (code "171") (name "Net-(IC25A-1A1)") (class "Default")
      (node (ref "IC25") (pin "47") (pinfunction "1A1_47") (pintype "input"))
      (node (ref "J1") (pin "C17") (pinfunction "C17_C17") (pintype "passive"))
    )
    (net (code "172") (name "Net-(IC25A-1A2)") (class "Default")
      (node (ref "IC25") (pin "46") (pinfunction "1A2_46") (pintype "input"))
      (node (ref "J1") (pin "C18") (pinfunction "C18_C18") (pintype "passive"))
    )
    (net (code "173") (name "Net-(IC25A-1A3)") (class "Default")
      (node (ref "IC25") (pin "44") (pinfunction "1A3_44") (pintype "input"))
      (node (ref "J1") (pin "C19") (pinfunction "C19_C19") (pintype "passive"))
    )
    (net (code "174") (name "Net-(IC25A-1A4)") (class "Default")
      (node (ref "IC25") (pin "43") (pinfunction "1A4_43") (pintype "input"))
      (node (ref "J1") (pin "C20") (pinfunction "C20_C20") (pintype "passive"))
    )
    (net (code "175") (name "Net-(IC25A-2A1)") (class "Default")
      (node (ref "IC25") (pin "41") (pinfunction "2A1_41") (pintype "input"))
      (node (ref "J1") (pin "C21") (pinfunction "C21_C21") (pintype "passive"))
    )
    (net (code "176") (name "Net-(IC25A-2A2)") (class "Default")
      (node (ref "IC25") (pin "40") (pinfunction "2A2_40") (pintype "input"))
      (node (ref "J1") (pin "C22") (pinfunction "C22_C22") (pintype "passive"))
    )
    (net (code "177") (name "Net-(IC25A-2A3)") (class "Default")
      (node (ref "IC25") (pin "38") (pinfunction "2A3_38") (pintype "input"))
      (node (ref "J1") (pin "C23") (pinfunction "C23_C23") (pintype "passive"))
    )
    (net (code "178") (name "Net-(IC25A-2A4)") (class "Default")
      (node (ref "IC25") (pin "37") (pinfunction "2A4_37") (pintype "input"))
      (node (ref "J1") (pin "C24") (pinfunction "C24_C24") (pintype "passive"))
    )
    (net (code "179") (name "Net-(IC25A-3A1)") (class "Default")
      (node (ref "IC25") (pin "36") (pinfunction "3A1_36") (pintype "input"))
      (node (ref "J1") (pin "C25") (pinfunction "C25_C25") (pintype "passive"))
    )
    (net (code "180") (name "Net-(IC25A-3A2)") (class "Default")
      (node (ref "IC25") (pin "35") (pinfunction "3A2_35") (pintype "input"))
      (node (ref "J1") (pin "C26") (pinfunction "C26_C26") (pintype "passive"))
    )
    (net (code "181") (name "Net-(IC25A-3A3)") (class "Default")
      (node (ref "IC25") (pin "33") (pinfunction "3A3_33") (pintype "input"))
      (node (ref "J1") (pin "C27") (pinfunction "C27_C27") (pintype "passive"))
    )
    (net (code "182") (name "Net-(IC25A-3A4)") (class "Default")
      (node (ref "IC25") (pin "32") (pinfunction "3A4_32") (pintype "input"))
      (node (ref "J1") (pin "C28") (pinfunction "C28_C28") (pintype "passive"))
    )
    (net (code "183") (name "Net-(IC25A-4A1)") (class "Default")
      (node (ref "IC25") (pin "30") (pinfunction "4A1_30") (pintype "input"))
      (node (ref "J1") (pin "C29") (pinfunction "C29_C29") (pintype "passive"))
    )
    (net (code "184") (name "Net-(IC25A-4A2)") (class "Default")
      (node (ref "IC25") (pin "29") (pinfunction "4A2_29") (pintype "input"))
      (node (ref "J1") (pin "C30") (pinfunction "C30_C30") (pintype "passive"))
    )
    (net (code "185") (name "Net-(IC25A-4A3)") (class "Default")
      (node (ref "IC25") (pin "27") (pinfunction "4A3_27") (pintype "input"))
      (node (ref "J1") (pin "C31") (pinfunction "C31_C31") (pintype "passive"))
    )
    (net (code "186") (name "Net-(IC25A-4A4)") (class "Default")
      (node (ref "IC25") (pin "26") (pinfunction "4A4_26") (pintype "input"))
      (node (ref "J1") (pin "C32") (pinfunction "C32_C32") (pintype "passive"))
    )
    (net (code "187") (name "Net-(IC26A-I0)") (class "Default")
      (node (ref "IC26") (pin "1") (pinfunction "I0_1") (pintype "input"))
      (node (ref "IC26") (pin "12") (pinfunction "I0_12") (pintype "input"))
      (node (ref "IC26") (pin "4") (pinfunction "I0_4") (pintype "input"))
      (node (ref "IC26") (pin "9") (pinfunction "I0_9") (pintype "input"))
      (node (ref "IC28") (pin "4") (pinfunction "O_4") (pintype "output"))
    )
    (net (code "188") (name "Net-(IC26A-I1)") (class "Default")
      (node (ref "IC2") (pin "1") (pinfunction "O_1") (pintype "output"))
      (node (ref "IC26") (pin "2") (pinfunction "I1_2") (pintype "input"))
    )
    (net (code "189") (name "Net-(IC26B-I1)") (class "Default")
      (node (ref "IC2") (pin "4") (pinfunction "O_4") (pintype "output"))
      (node (ref "IC26") (pin "5") (pinfunction "I1_5") (pintype "input"))
    )
    (net (code "190") (name "Net-(IC26C-I1)") (class "Default")
      (node (ref "IC2") (pin "10") (pinfunction "O_10") (pintype "output"))
      (node (ref "IC26") (pin "10") (pinfunction "I1_10") (pintype "input"))
    )
    (net (code "191") (name "Net-(IC26D-I1)") (class "Default")
      (node (ref "IC2") (pin "13") (pinfunction "O_13") (pintype "output"))
      (node (ref "IC26") (pin "13") (pinfunction "I1_13") (pintype "input"))
    )
    (net (code "192") (name "Net-(IC27A-O)") (class "Default")
      (node (ref "IC2") (pin "11") (pinfunction "I0_11") (pintype "input"))
      (node (ref "IC2") (pin "5") (pinfunction "I0_5") (pintype "input"))
      (node (ref "IC27") (pin "2") (pinfunction "O_2") (pintype "output"))
    )
    (net (code "193") (name "Net-(IC27B-O)") (class "Default")
      (node (ref "IC2") (pin "12") (pinfunction "I1_12") (pintype "input"))
      (node (ref "IC2") (pin "9") (pinfunction "I1_9") (pintype "input"))
      (node (ref "IC27") (pin "4") (pinfunction "O_4") (pintype "output"))
    )
    (net (code "194") (name "Net-(IC27D-O)") (class "Default")
      (node (ref "IC27") (pin "8") (pinfunction "O_8") (pintype "output"))
      (node (ref "U$1") (pin "7") (pinfunction "~{S}_7") (pintype "input"))
    )
    (net (code "195") (name "Net-(IC27E-O)") (class "Default")
      (node (ref "IC27") (pin "10") (pinfunction "O_10") (pintype "output"))
      (node (ref "U$1") (pin "6") (pinfunction "~{R}_6") (pintype "input"))
    )
    (net (code "196") (name "Net-(IC27F-O)") (class "Default")
      (node (ref "IC27") (pin "12") (pinfunction "O_12") (pintype "output"))
      (node (ref "IC34") (pin "2") (pinfunction "I1_2") (pintype "input"))
    )
    (net (code "197") (name "Net-(IC29A-1C)") (class "Default")
      (node (ref "IC29") (pin "25") (pinfunction "2C_25") (pintype "input"))
      (node (ref "IC29") (pin "48") (pinfunction "1C_48") (pintype "input"))
      (node (ref "IC38") (pin "4") (pinfunction "O_4") (pintype "output"))
    )
    (net (code "198") (name "Net-(IC29A-1D3)") (class "Default")
      (node (ref "IC29") (pin "44") (pinfunction "1D3_44") (pintype "input"))
      (node (ref "IC37") (pin "4") (pinfunction "O_4") (pintype "output"))
    )
    (net (code "199") (name "Net-(IC30A-I0)") (class "Default")
      (node (ref "IC30") (pin "1") (pinfunction "I0_1") (pintype "input"))
      (node (ref "IC31") (pin "1") (pinfunction "I0_1") (pintype "input"))
      (node (ref "IC45") (pin "4") (pinfunction "O_4") (pintype "output"))
    )
    (net (code "200") (name "Net-(IC30A-I1)") (class "Default")
      (node (ref "IC30") (pin "2") (pinfunction "I1_2") (pintype "input"))
      (node (ref "IC32") (pin "1") (pinfunction "I0_1") (pintype "input"))
      (node (ref "U$1") (pin "5") (pinfunction "Q_5") (pintype "output"))
    )
    (net (code "201") (name "Net-(IC31A-I1)") (class "Default")
      (node (ref "IC31") (pin "2") (pinfunction "I1_2") (pintype "input"))
      (node (ref "U$1") (pin "3") (pinfunction "~{Q}_3") (pintype "output"))
    )
    (net (code "202") (name "Net-(IC32A-O)") (class "Default")
      (node (ref "IC32") (pin "4") (pinfunction "O_4") (pintype "output"))
      (node (ref "IC36") (pin "1") (pinfunction "I0_1") (pintype "input"))
    )
    (net (code "203") (name "Net-(IC34A-I0)") (class "Default")
      (node (ref "IC34") (pin "1") (pinfunction "I0_1") (pintype "input"))
      (node (ref "IC46") (pin "4") (pinfunction "O_4") (pintype "output"))
    )
    (net (code "204") (name "Net-(IC34A-O)") (class "Default")
      (node (ref "IC34") (pin "4") (pinfunction "O_4") (pintype "output"))
      (node (ref "IC36") (pin "2") (pinfunction "I1_2") (pintype "input"))
    )
    (net (code "205") (name "Net-(IC35A-O)") (class "Default")
      (node (ref "IC35") (pin "4") (pinfunction "O_4") (pintype "output"))
      (node (ref "IC8") (pin "2") (pinfunction "I1_2") (pintype "input"))
    )
    (net (code "206") (name "Net-(IC37A-I1)") (class "Default")
      (node (ref "IC37") (pin "2") (pinfunction "I1_2") (pintype "input"))
      (node (ref "IC40") (pin "4") (pinfunction "O_4") (pintype "output"))
    )
    (net (code "207") (name "Net-(IC38A-I0)") (class "Default")
      (node (ref "IC38") (pin "1") (pinfunction "I0_1") (pintype "input"))
      (node (ref "IC39") (pin "4") (pinfunction "O_4") (pintype "output"))
    )
    (net (code "208") (name "Net-(IC39A-I)") (class "Default")
      (node (ref "C12") (pin "1") (pinfunction "1_1") (pintype "passive"))
      (node (ref "D2") (pin "A") (pinfunction "A_A") (pintype "passive"))
      (node (ref "IC39") (pin "2") (pinfunction "I_2") (pintype "input"))
      (node (ref "R1") (pin "2") (pinfunction "2_2") (pintype "passive"))
    )
    (net (code "209") (name "Net-(IC40A-I)") (class "Default")
      (node (ref "C11") (pin "1") (pinfunction "1_1") (pintype "passive"))
      (node (ref "D1") (pin "A") (pinfunction "A_A") (pintype "passive"))
      (node (ref "IC40") (pin "2") (pinfunction "I_2") (pintype "input"))
      (node (ref "R3") (pin "2") (pinfunction "2_2") (pintype "passive"))
    )
    (net (code "210") (name "Net-(IC41A-O)") (class "Default")
      (node (ref "IC41") (pin "4") (pinfunction "O_4") (pintype "output"))
      (node (ref "R5") (pin "2") (pinfunction "2_2") (pintype "passive"))
    )
    (net (code "211") (name "Net-(IC42A-O)") (class "Default")
      (node (ref "IC42") (pin "4") (pinfunction "O_4") (pintype "output"))
      (node (ref "R4") (pin "2") (pinfunction "2_2") (pintype "passive"))
    )
    (net (code "212") (name "Net-(IC43A-O)") (class "Default")
      (node (ref "IC43") (pin "4") (pinfunction "O_4") (pintype "output"))
      (node (ref "R2") (pin "2") (pinfunction "2_2") (pintype "passive"))
    )
    (net (code "213") (name "Net-(IC44A-O)") (class "Default")
      (node (ref "IC44") (pin "4") (pinfunction "O_4") (pintype "output"))
      (node (ref "U$3") (pin "1") (pinfunction "1_1") (pintype "passive"))
    )
    (net (code "214") (name "Net-(LED1-PadA)") (class "Default")
      (node (ref "LED1") (pin "A") (pinfunction "A_A") (pintype "passive"))
      (node (ref "R5") (pin "1") (pinfunction "1_1") (pintype "passive"))
    )
    (net (code "215") (name "Net-(LED2-PadA)") (class "Default")
      (node (ref "LED2") (pin "A") (pinfunction "A_A") (pintype "passive"))
      (node (ref "R4") (pin "1") (pinfunction "1_1") (pintype "passive"))
    )
    (net (code "216") (name "Net-(LED3-PadA)") (class "Default")
      (node (ref "LED3") (pin "A") (pinfunction "A_A") (pintype "passive"))
      (node (ref "R2") (pin "1") (pinfunction "1_1") (pintype "passive"))
    )
    (net (code "217") (name "Net-(Q1-OUT)") (class "Default")
      (node (ref "JP1") (pin "1") (pinfunction "1_1") (pintype "passive"))
      (node (ref "Q1") (pin "3") (pinfunction "OUT_3") (pintype "output"))
      (node (ref "U$2") (pin "1") (pinfunction "CLK_1") (pintype "input"))
    )
    (net (code "218") (name "Net-(U$2A-D)") (class "Default")
      (node (ref "U$2") (pin "2") (pinfunction "D_2") (pintype "input"))
      (node (ref "U$2") (pin "3") (pinfunction "~{Q}_3") (pintype "output"))
    )
    (net (code "219") (name "Net-(U$2A-Q)") (class "Default")
      (node (ref "JP1") (pin "3") (pinfunction "3_3") (pintype "passive"))
      (node (ref "U$2") (pin "5") (pinfunction "Q_5") (pintype "output"))
    )
    (net (code "220") (name "PROG") (class "Default")
      (node (ref "IC25") (pin "16") (pinfunction "3Y3_16") (pintype "tri_state"))
      (node (ref "IC27") (pin "13") (pinfunction "I_13") (pintype "input"))
    )
    (net (code "221") (name "RES") (class "Default")
      (node (ref "IC15") (pin "1") (pinfunction "I0_1") (pintype "input"))
      (node (ref "IC23") (pin "1") (pinfunction "I0_1") (pintype "input"))
      (node (ref "IC25") (pin "17") (pinfunction "3Y4_17") (pintype "tri_state"))
    )
    (net (code "222") (name "TRIG_ENBL") (class "Default")
      (node (ref "IC29") (pin "6") (pinfunction "1Q4_6") (pintype "tri_state"))
      (node (ref "IC35") (pin "1") (pinfunction "I0_1") (pintype "input"))
    )
    (net (code "223") (name "TX") (class "Default")
      (node (ref "IC35") (pin "2") (pinfunction "I1_2") (pintype "input"))
      (node (ref "IC36") (pin "4") (pinfunction "O_4") (pintype "output"))
      (node (ref "IC42") (pin "2") (pinfunction "I_2") (pintype "input"))
      (node (ref "IC44") (pin "2") (pinfunction "I_2") (pintype "input"))
      (node (ref "J1") (pin "A8") (pinfunction "A8_A8") (pintype "passive"))
    )
    (net (code "224") (name "UBL_ENBL") (class "Default")
      (node (ref "IC29") (pin "5") (pinfunction "1Q3_5") (pintype "tri_state"))
      (node (ref "IC46") (pin "2") (pinfunction "I1_2") (pintype "input"))
    )
    (net (code "225") (name "VCC") (class "Default")
      (node (ref "C1") (pin "1") (pinfunction "1_1") (pintype "passive"))
      (node (ref "C10") (pin "1") (pinfunction "1_1") (pintype "passive"))
      (node (ref "C14") (pin "1") (pinfunction "1_1") (pintype "passive"))
      (node (ref "C15") (pin "1") (pinfunction "1_1") (pintype "passive"))
      (node (ref "C16") (pin "1") (pinfunction "1_1") (pintype "passive"))
      (node (ref "C17") (pin "1") (pinfunction "1_1") (pintype "passive"))
      (node (ref "C18") (pin "1") (pinfunction "1_1") (pintype "passive"))
      (node (ref "C19") (pin "1") (pinfunction "1_1") (pintype "passive"))
      (node (ref "C2") (pin "1") (pinfunction "1_1") (pintype "passive"))
      (node (ref "C20") (pin "1") (pinfunction "1_1") (pintype "passive"))
      (node (ref "C21") (pin "1") (pinfunction "1_1") (pintype "passive"))
      (node (ref "C22") (pin "1") (pinfunction "1_1") (pintype "passive"))
      (node (ref "C23") (pin "1") (pinfunction "1_1") (pintype "passive"))
      (node (ref "C24") (pin "1") (pinfunction "1_1") (pintype "passive"))
      (node (ref "C25") (pin "1") (pinfunction "1_1") (pintype "passive"))
      (node (ref "C26") (pin "1") (pinfunction "1_1") (pintype "passive"))
      (node (ref "C27") (pin "1") (pinfunction "1_1") (pintype "passive"))
      (node (ref "C28") (pin "1") (pinfunction "1_1") (pintype "passive"))
      (node (ref "C29") (pin "1") (pinfunction "1_1") (pintype "passive"))
      (node (ref "C3") (pin "1") (pinfunction "1_1") (pintype "passive"))
      (node (ref "C4") (pin "1") (pinfunction "1_1") (pintype "passive"))
      (node (ref "C5") (pin "1") (pinfunction "1_1") (pintype "passive"))
      (node (ref "C6") (pin "1") (pinfunction "1_1") (pintype "passive"))
      (node (ref "C7") (pin "1") (pinfunction "1_1") (pintype "passive"))
      (node (ref "C8") (pin "1") (pinfunction "1_1") (pintype "passive"))
      (node (ref "C9") (pin "1") (pinfunction "1_1") (pintype "passive"))
      (node (ref "D1") (pin "C") (pinfunction "C_C") (pintype "passive"))
      (node (ref "D2") (pin "C") (pinfunction "C_C") (pintype "passive"))
      (node (ref "Q1") (pin "4") (pinfunction "VDD_4") (pintype "power_in"))
      (node (ref "R1") (pin "1") (pinfunction "1_1") (pintype "passive"))
      (node (ref "R3") (pin "1") (pinfunction "1_1") (pintype "passive"))
      (node (ref "S1") (pin "1") (pinfunction "1_1") (pintype "passive"))
      (node (ref "S1") (pin "2") (pinfunction "2_2") (pintype "passive"))
      (node (ref "S1") (pin "3") (pinfunction "3_3") (pintype "passive"))
      (node (ref "S1") (pin "4") (pinfunction "4_4") (pintype "passive"))
      (node (ref "S1") (pin "5") (pinfunction "5_5") (pintype "passive"))
      (node (ref "S1") (pin "6") (pinfunction "6_6") (pintype "passive"))
      (node (ref "S1") (pin "7") (pinfunction "7_7") (pintype "passive"))
      (node (ref "S1") (pin "8") (pinfunction "8_8") (pintype "passive"))
      (node (ref "U$2") (pin "6") (pinfunction "~{R}_6") (pintype "input"))
      (node (ref "U$2") (pin "7") (pinfunction "~{S}_7") (pintype "input"))
      (node (ref "U$9") (pin "2") (pinfunction "VCC_2") (pintype "power_in"))
      (node (ref "U$9") (pin "4") (pinfunction "VCC_4") (pintype "power_in"))
    )
    (net (code "226") (name "WE") (class "Default")
      (node (ref "IC25") (pin "20") (pinfunction "4Y2_20") (pintype "tri_state"))
      (node (ref "IC28") (pin "1") (pinfunction "I0_1") (pintype "input"))
    )
    (net (code "227") (name "W_A") (class "Default")
      (node (ref "IC26") (pin "3") (pinfunction "O_3") (pintype "output"))
      (node (ref "IC38") (pin "2") (pinfunction "I1_2") (pintype "input"))
    )
    (net (code "228") (name "W_B") (class "Default")
      (node (ref "IC26") (pin "6") (pinfunction "O_6") (pintype "output"))
      (node (ref "IC7") (pin "25") (pinfunction "2C_25") (pintype "input"))
      (node (ref "IC7") (pin "48") (pinfunction "1C_48") (pintype "input"))
    )
    (net (code "229") (name "W_C") (class "Default")
      (node (ref "IC22") (pin "25") (pinfunction "2C_25") (pintype "input"))
      (node (ref "IC22") (pin "48") (pinfunction "1C_48") (pintype "input"))
      (node (ref "IC26") (pin "8") (pinfunction "O_8") (pintype "output"))
    )
    (net (code "230") (name "W_D") (class "Default")
      (node (ref "IC14") (pin "25") (pinfunction "2C_25") (pintype "input"))
      (node (ref "IC14") (pin "48") (pinfunction "1C_48") (pintype "input"))
      (node (ref "IC26") (pin "11") (pinfunction "O_11") (pintype "output"))
    )
    (net (code "231") (name "unconnected-(IC25A-4Y1-Pad19)") (class "Default")
      (node (ref "IC25") (pin "19") (pinfunction "4Y1_19") (pintype "tri_state"))
    )
    (net (code "232") (name "unconnected-(IC25A-4Y3-Pad22)") (class "Default")
      (node (ref "IC25") (pin "22") (pinfunction "4Y3_22") (pintype "tri_state"))
    )
    (net (code "233") (name "unconnected-(IC29A-1Q5-Pad8)") (class "Default")
      (node (ref "IC29") (pin "8") (pinfunction "1Q5_8") (pintype "tri_state"))
    )
    (net (code "234") (name "unconnected-(IC29A-1Q6-Pad9)") (class "Default")
      (node (ref "IC29") (pin "9") (pinfunction "1Q6_9") (pintype "tri_state"))
    )
    (net (code "235") (name "unconnected-(IC29A-1Q7-Pad11)") (class "Default")
      (node (ref "IC29") (pin "11") (pinfunction "1Q7_11") (pintype "tri_state"))
    )
    (net (code "236") (name "unconnected-(IC29A-1Q8-Pad12)") (class "Default")
      (node (ref "IC29") (pin "12") (pinfunction "1Q8_12") (pintype "tri_state"))
    )
    (net (code "237") (name "unconnected-(IC29A-2Q1-Pad13)") (class "Default")
      (node (ref "IC29") (pin "13") (pinfunction "2Q1_13") (pintype "tri_state"))
    )
    (net (code "238") (name "unconnected-(IC29A-2Q2-Pad14)") (class "Default")
      (node (ref "IC29") (pin "14") (pinfunction "2Q2_14") (pintype "tri_state"))
    )
    (net (code "239") (name "unconnected-(IC29A-2Q3-Pad16)") (class "Default")
      (node (ref "IC29") (pin "16") (pinfunction "2Q3_16") (pintype "tri_state"))
    )
    (net (code "240") (name "unconnected-(IC29A-2Q4-Pad17)") (class "Default")
      (node (ref "IC29") (pin "17") (pinfunction "2Q4_17") (pintype "tri_state"))
    )
    (net (code "241") (name "unconnected-(IC29A-2Q5-Pad19)") (class "Default")
      (node (ref "IC29") (pin "19") (pinfunction "2Q5_19") (pintype "tri_state"))
    )
    (net (code "242") (name "unconnected-(IC29A-2Q6-Pad20)") (class "Default")
      (node (ref "IC29") (pin "20") (pinfunction "2Q6_20") (pintype "tri_state"))
    )
    (net (code "243") (name "unconnected-(IC29A-2Q7-Pad22)") (class "Default")
      (node (ref "IC29") (pin "22") (pinfunction "2Q7_22") (pintype "tri_state"))
    )
    (net (code "244") (name "unconnected-(IC29A-2Q8-Pad23)") (class "Default")
      (node (ref "IC29") (pin "23") (pinfunction "2Q8_23") (pintype "tri_state"))
    )
    (net (code "245") (name "unconnected-(J1-PadA1)") (class "Default")
      (node (ref "J1") (pin "A1") (pinfunction "A1_A1") (pintype "passive"))
    )
    (net (code "246") (name "unconnected-(J1-PadA2)") (class "Default")
      (node (ref "J1") (pin "A2") (pinfunction "A2_A2") (pintype "passive"))
    )
    (net (code "247") (name "unconnected-(J1-PadA3)") (class "Default")
      (node (ref "J1") (pin "A3") (pinfunction "A3_A3") (pintype "passive"))
    )
    (net (code "248") (name "unconnected-(J1-PadA4)") (class "Default")
      (node (ref "J1") (pin "A4") (pinfunction "A4_A4") (pintype "passive"))
    )
    (net (code "249") (name "unconnected-(J1-PadA5)") (class "Default")
      (node (ref "J1") (pin "A5") (pinfunction "A5_A5") (pintype "passive"))
    )
    (net (code "250") (name "unconnected-(J1-PadA6)") (class "Default")
      (node (ref "J1") (pin "A6") (pinfunction "A6_A6") (pintype "passive"))
    )
    (net (code "251") (name "unconnected-(J1-PadA7)") (class "Default")
      (node (ref "J1") (pin "A7") (pinfunction "A7_A7") (pintype "passive"))
    )
    (net (code "252") (name "unconnected-(J1-PadA25)") (class "Default")
      (node (ref "J1") (pin "A25") (pinfunction "A25_A25") (pintype "passive"))
    )
    (net (code "253") (name "unconnected-(J1-PadA26)") (class "Default")
      (node (ref "J1") (pin "A26") (pinfunction "A26_A26") (pintype "passive"))
    )
  )
)
